# enzi_rev3.net
KiCad netlist of a schematic drawn in EAGLE
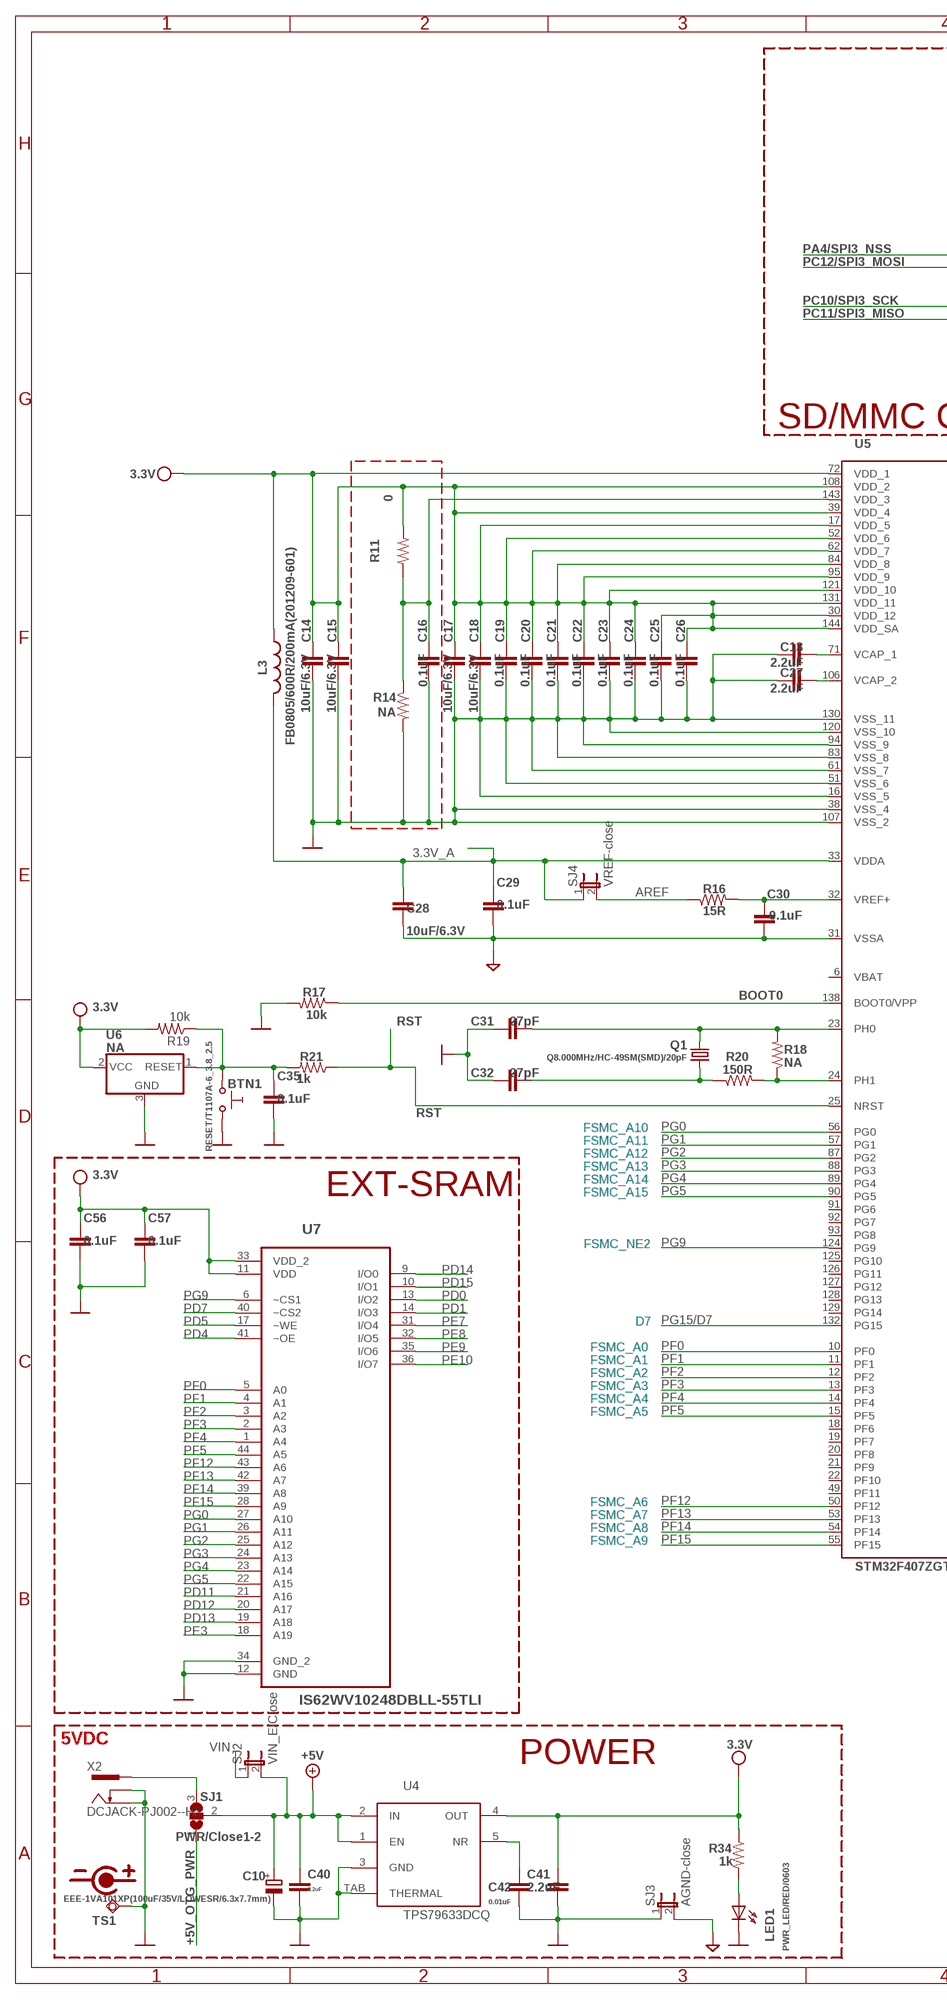
[diagram p0: schematic, sheet 1, part 1 of 2]
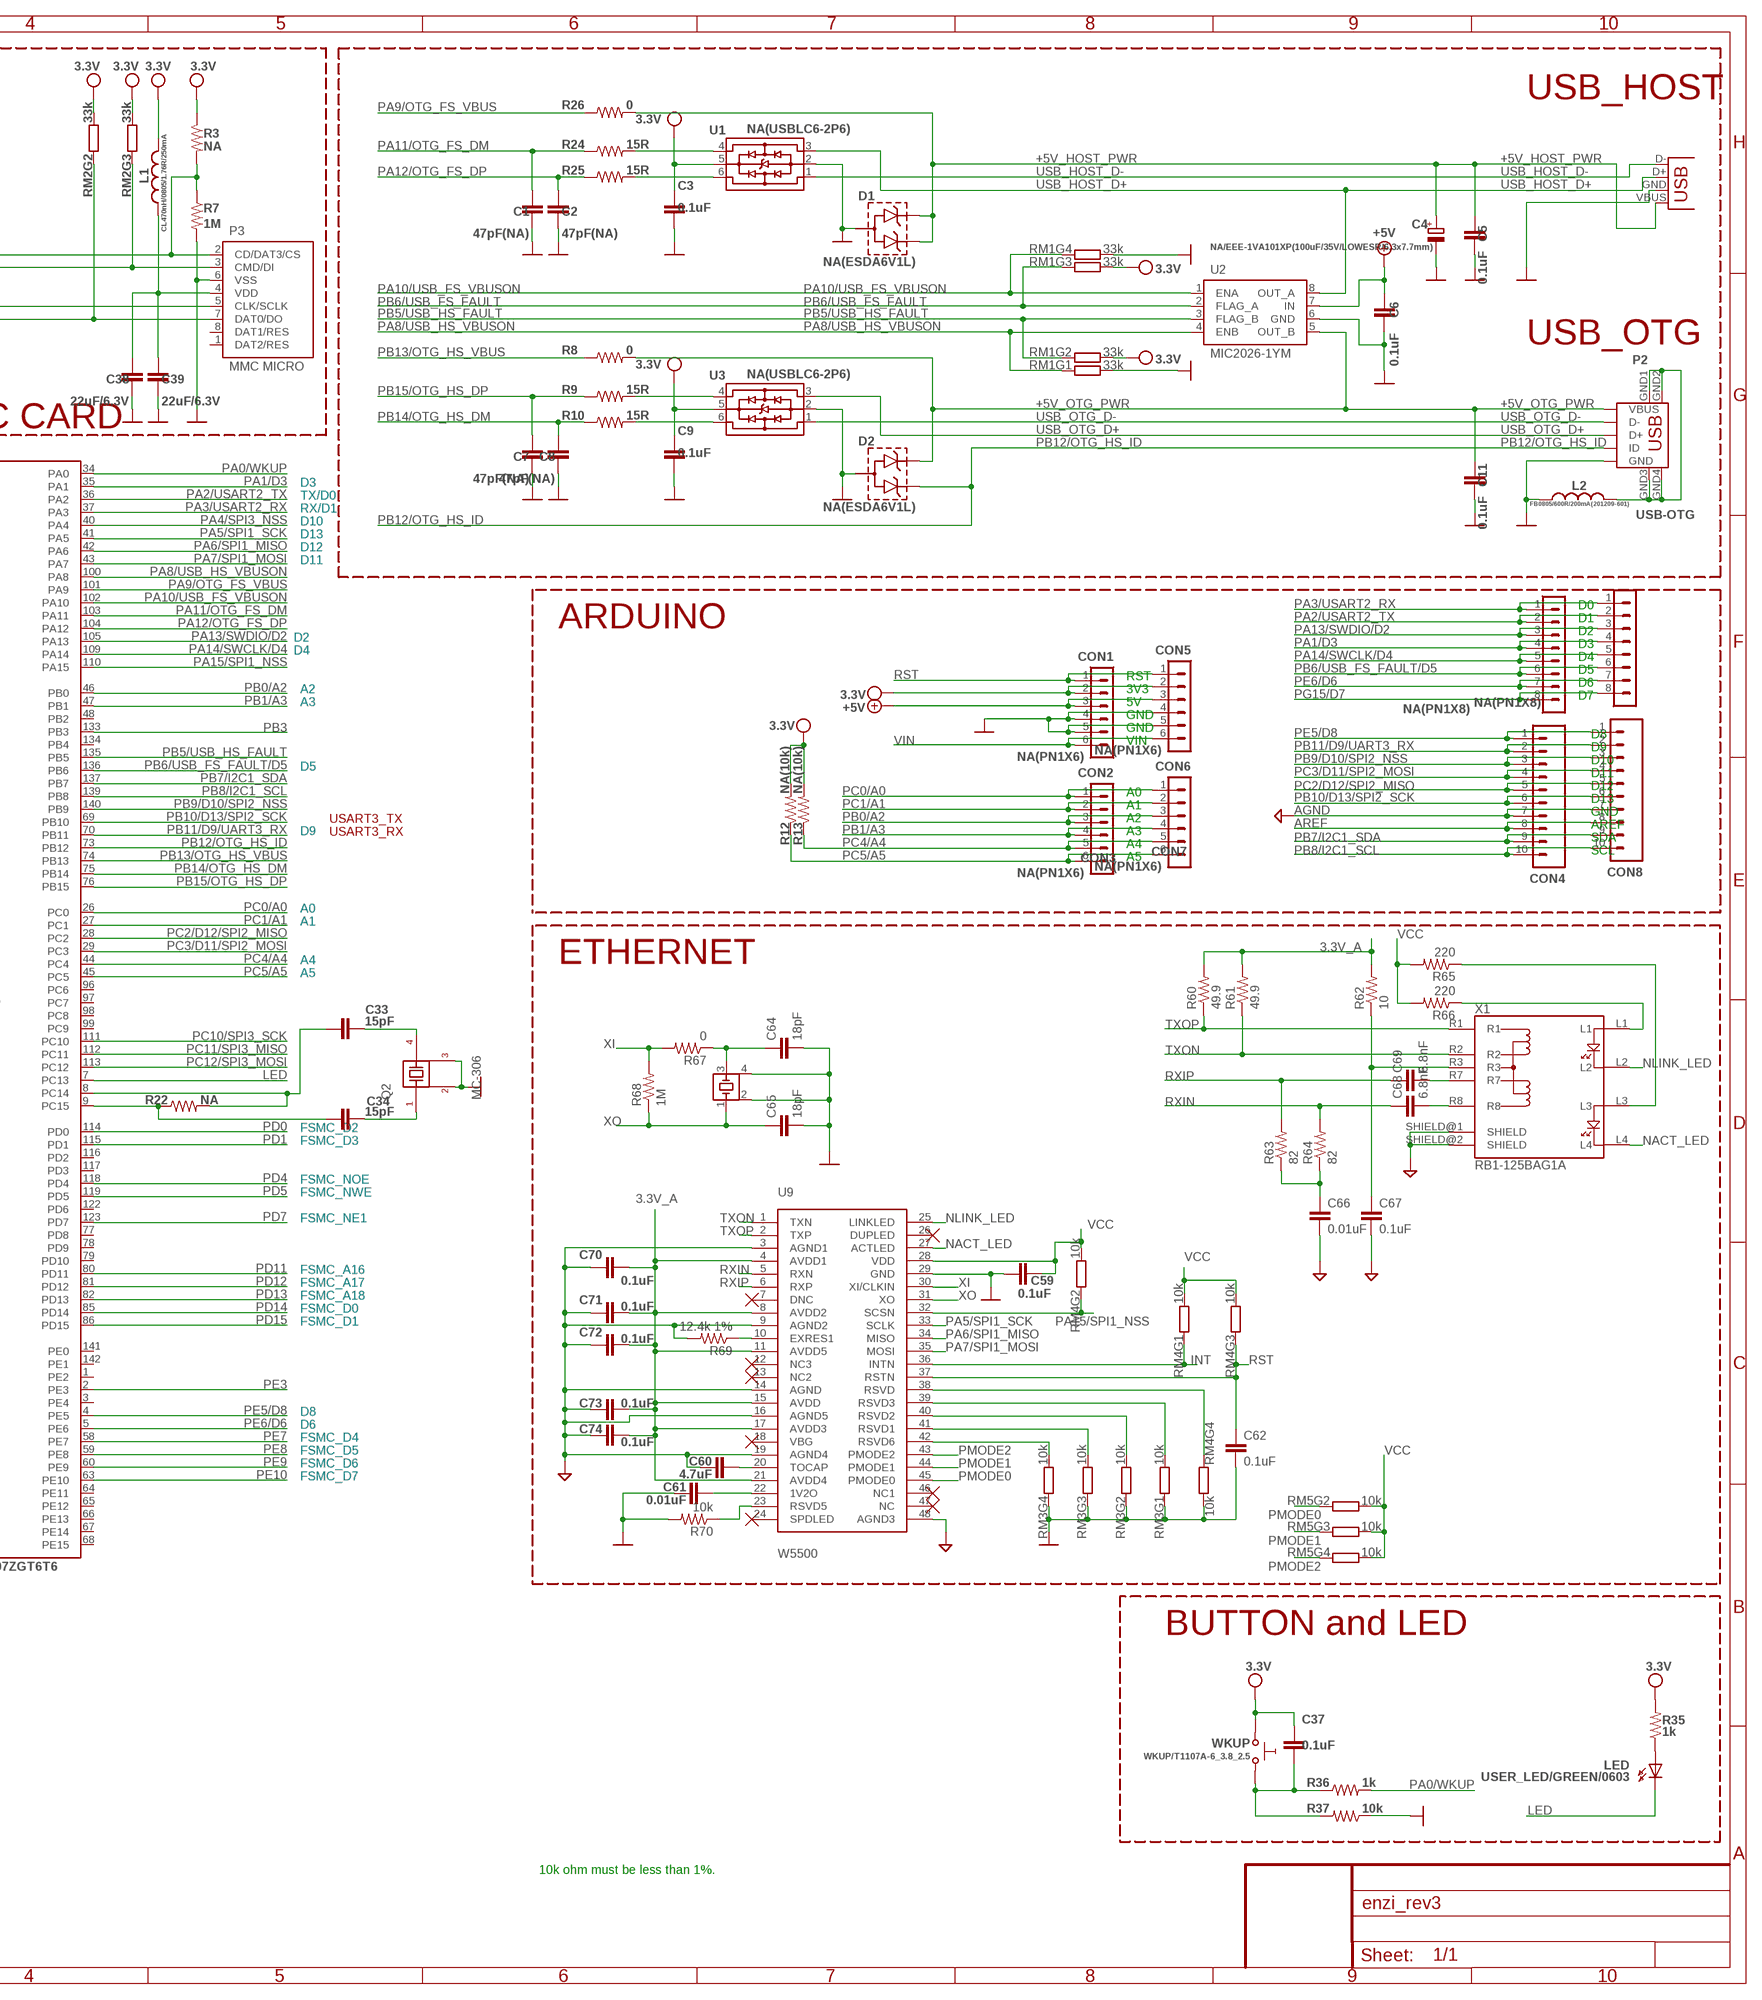
[diagram p1: schematic, sheet 1, part 2 of 2]

(export (version "E")
  (design (tool "Eeschema 10.0.6"))
  (components
    (comp (ref "BTN1")
      (value "RESET/T1107A-6_3.8_2.5")
      (footprint "eagle-import:SW-TAKT_6X3.5_SMD")
      (libsource (lib "eagle-import") (part "SW-TAKT6"))
    )
    (comp (ref "C1")
      (value "47pF(NA)")
      (footprint "eagle-import:0603-CAP")
      (libsource (lib "eagle-import") (part "CAP0603-CAP"))
    )
    (comp (ref "C2")
      (value "47pF(NA)")
      (footprint "eagle-import:0603-CAP")
      (libsource (lib "eagle-import") (part "CAP0603-CAP"))
    )
    (comp (ref "C3")
      (value "0.1uF")
      (footprint "eagle-import:0603-CAP")
      (libsource (lib "eagle-import") (part "CAP0603-CAP"))
    )
    (comp (ref "C4")
      (value "NA/EEE-1VA101XP(100uF/35V/LOWESR/6.3x7.7mm)")
      (footprint "eagle-import:PANASONIC_D")
      (libsource (lib "eagle-import") (part "CPOL-EUD"))
    )
    (comp (ref "C5")
      (value "0.1uF")
      (footprint "eagle-import:0603-CAP")
      (libsource (lib "eagle-import") (part "CAP0603-CAP"))
    )
    (comp (ref "C6")
      (value "0.1uF")
      (footprint "eagle-import:0603-CAP")
      (libsource (lib "eagle-import") (part "CAP0603-CAP"))
    )
    (comp (ref "C7")
      (value "47pF(NA)")
      (footprint "eagle-import:0603-CAP")
      (libsource (lib "eagle-import") (part "CAP0603-CAP"))
    )
    (comp (ref "C8")
      (value "47pF(NA)")
      (footprint "eagle-import:0603-CAP")
      (libsource (lib "eagle-import") (part "CAP0603-CAP"))
    )
    (comp (ref "C9")
      (value "0.1uF")
      (footprint "eagle-import:0603-CAP")
      (libsource (lib "eagle-import") (part "CAP0603-CAP"))
    )
    (comp (ref "C10")
      (value "EEE-1VA101XP(100uF/35V/LOWESR/6.3x7.7mm)")
      (footprint "eagle-import:PANASONIC_D")
      (libsource (lib "eagle-import") (part "CPOL-EUD"))
    )
    (comp (ref "C11")
      (value "0.1uF")
      (footprint "eagle-import:0603-CAP")
      (libsource (lib "eagle-import") (part "CAP0603-CAP"))
    )
    (comp (ref "C13")
      (value "2.2uF")
      (footprint "eagle-import:0603-CAP")
      (libsource (lib "eagle-import") (part "CAP0603-CAP"))
    )
    (comp (ref "C14")
      (value "10uF/6.3V")
      (footprint "eagle-import:0603-CAP")
      (libsource (lib "eagle-import") (part "CAP0603-CAP"))
    )
    (comp (ref "C15")
      (value "10uF/6.3V")
      (footprint "eagle-import:0603-CAP")
      (libsource (lib "eagle-import") (part "CAP0603-CAP"))
    )
    (comp (ref "C16")
      (value "0.1uF")
      (footprint "eagle-import:0603-CAP")
      (libsource (lib "eagle-import") (part "CAP0603-CAP"))
    )
    (comp (ref "C17")
      (value "10uF/6.3V")
      (footprint "eagle-import:0603-CAP")
      (libsource (lib "eagle-import") (part "CAP0603-CAP"))
    )
    (comp (ref "C18")
      (value "10uF/6.3V")
      (footprint "eagle-import:0603-CAP")
      (libsource (lib "eagle-import") (part "CAP0603-CAP"))
    )
    (comp (ref "C19")
      (value "0.1uF")
      (footprint "eagle-import:0603-CAP")
      (libsource (lib "eagle-import") (part "CAP0603-CAP"))
    )
    (comp (ref "C20")
      (value "0.1uF")
      (footprint "eagle-import:0603-CAP")
      (libsource (lib "eagle-import") (part "CAP0603-CAP"))
    )
    (comp (ref "C21")
      (value "0.1uF")
      (footprint "eagle-import:0603-CAP")
      (libsource (lib "eagle-import") (part "CAP0603-CAP"))
    )
    (comp (ref "C22")
      (value "0.1uF")
      (footprint "eagle-import:0603-CAP")
      (libsource (lib "eagle-import") (part "CAP0603-CAP"))
    )
    (comp (ref "C23")
      (value "0.1uF")
      (footprint "eagle-import:0603-CAP")
      (libsource (lib "eagle-import") (part "CAP0603-CAP"))
    )
    (comp (ref "C24")
      (value "0.1uF")
      (footprint "eagle-import:0603-CAP")
      (libsource (lib "eagle-import") (part "CAP0603-CAP"))
    )
    (comp (ref "C25")
      (value "0.1uF")
      (footprint "eagle-import:0603-CAP")
      (libsource (lib "eagle-import") (part "CAP0603-CAP"))
    )
    (comp (ref "C26")
      (value "0.1uF")
      (footprint "eagle-import:0603-CAP")
      (libsource (lib "eagle-import") (part "CAP0603-CAP"))
    )
    (comp (ref "C27")
      (value "2.2uF")
      (footprint "eagle-import:0603-CAP")
      (libsource (lib "eagle-import") (part "CAP0603-CAP"))
    )
    (comp (ref "C28")
      (value "10uF/6.3V")
      (footprint "eagle-import:0603-CAP")
      (libsource (lib "eagle-import") (part "CAP0603-CAP"))
    )
    (comp (ref "C29")
      (value "0.1uF")
      (footprint "eagle-import:0603-CAP")
      (libsource (lib "eagle-import") (part "CAP0603-CAP"))
    )
    (comp (ref "C30")
      (value "0.1uF")
      (footprint "eagle-import:0603-CAP")
      (libsource (lib "eagle-import") (part "CAP0603-CAP"))
    )
    (comp (ref "C31")
      (value "27pF")
      (footprint "eagle-import:0603-CAP")
      (libsource (lib "eagle-import") (part "CAP0603-CAP"))
    )
    (comp (ref "C32")
      (value "27pF")
      (footprint "eagle-import:0603-CAP")
      (libsource (lib "eagle-import") (part "CAP0603-CAP"))
    )
    (comp (ref "C33")
      (value "15pF")
      (footprint "eagle-import:0603-CAP")
      (libsource (lib "eagle-import") (part "CAP0603-CAP"))
    )
    (comp (ref "C34")
      (value "15pF")
      (footprint "eagle-import:0603-CAP")
      (libsource (lib "eagle-import") (part "CAP0603-CAP"))
    )
    (comp (ref "C35")
      (value "0.1uF")
      (footprint "eagle-import:0603-CAP")
      (libsource (lib "eagle-import") (part "CAP0603-CAP"))
    )
    (comp (ref "C37")
      (value "0.1uF")
      (footprint "eagle-import:0603-CAP")
      (libsource (lib "eagle-import") (part "CAP0603-CAP"))
    )
    (comp (ref "C38")
      (value "22uF/6.3V")
      (footprint "eagle-import:0603-CAP")
      (libsource (lib "eagle-import") (part "CAP0603-CAP"))
    )
    (comp (ref "C39")
      (value "22uF/6.3V")
      (footprint "eagle-import:0603-CAP")
      (libsource (lib "eagle-import") (part "CAP0603-CAP"))
    )
    (comp (ref "C40")
      (value "2.2uF")
      (footprint "eagle-import:0603-CAP")
      (libsource (lib "eagle-import") (part "CAP0603-CAP"))
    )
    (comp (ref "C41")
      (value "2.2uF")
      (footprint "eagle-import:0603-CAP")
      (libsource (lib "eagle-import") (part "CAP0603-CAP"))
    )
    (comp (ref "C42")
      (value "0.01uF")
      (footprint "eagle-import:0603-CAP")
      (libsource (lib "eagle-import") (part "CAP0603-CAP"))
    )
    (comp (ref "C56")
      (value "0.1uF")
      (footprint "eagle-import:0603-CAP")
      (libsource (lib "eagle-import") (part "CAP0603-CAP"))
    )
    (comp (ref "C57")
      (value "0.1uF")
      (footprint "eagle-import:0603-CAP")
      (libsource (lib "eagle-import") (part "CAP0603-CAP"))
    )
    (comp (ref "C59")
      (value "0.1uF")
      (footprint "eagle-import:0603-CAP")
      (libsource (lib "eagle-import") (part "CAP0603-CAP"))
    )
    (comp (ref "C60")
      (value "4.7uF")
      (footprint "eagle-import:0603-CAP")
      (libsource (lib "eagle-import") (part "CAP0603-CAP"))
    )
    (comp (ref "C61")
      (value "0.01uF")
      (footprint "eagle-import:0603-CAP")
      (libsource (lib "eagle-import") (part "CAP0603-CAP"))
    )
    (comp (ref "C62")
      (value "0.1uF")
      (footprint "eagle-import:0603-CAP")
      (libsource (lib "eagle-import") (part "CAP0603-CAP"))
    )
    (comp (ref "C64")
      (value "18pF")
      (footprint "eagle-import:0603-CAP")
      (libsource (lib "eagle-import") (part "CAP0603-CAP"))
    )
    (comp (ref "C65")
      (value "18pF")
      (footprint "eagle-import:0603-CAP")
      (libsource (lib "eagle-import") (part "CAP0603-CAP"))
    )
    (comp (ref "C66")
      (value "0.01uF")
      (footprint "eagle-import:0603-CAP")
      (libsource (lib "eagle-import") (part "CAP0603-CAP"))
    )
    (comp (ref "C67")
      (value "0.1uF")
      (footprint "eagle-import:0603-CAP")
      (libsource (lib "eagle-import") (part "CAP0603-CAP"))
    )
    (comp (ref "C68")
      (value "6.8nF")
      (footprint "eagle-import:0603-CAP")
      (libsource (lib "eagle-import") (part "CAP0603-CAP"))
    )
    (comp (ref "C69")
      (value "6.8nF")
      (footprint "eagle-import:0603-CAP")
      (libsource (lib "eagle-import") (part "CAP0603-CAP"))
    )
    (comp (ref "C70")
      (value "0.1uF")
      (footprint "eagle-import:0603-CAP")
      (libsource (lib "eagle-import") (part "CAP0603-CAP"))
    )
    (comp (ref "C71")
      (value "0.1uF")
      (footprint "eagle-import:0603-CAP")
      (libsource (lib "eagle-import") (part "CAP0603-CAP"))
    )
    (comp (ref "C72")
      (value "0.1uF")
      (footprint "eagle-import:0603-CAP")
      (libsource (lib "eagle-import") (part "CAP0603-CAP"))
    )
    (comp (ref "C73")
      (value "0.1uF")
      (footprint "eagle-import:0603-CAP")
      (libsource (lib "eagle-import") (part "CAP0603-CAP"))
    )
    (comp (ref "C74")
      (value "0.1uF")
      (footprint "eagle-import:0603-CAP")
      (libsource (lib "eagle-import") (part "CAP0603-CAP"))
    )
    (comp (ref "CON1")
      (value "NA(PN1X6)")
      (footprint "eagle-import:PN1X6")
      (libsource (lib "eagle-import") (part "CON6PN1X6"))
    )
    (comp (ref "CON2")
      (value "NA(PN1X6)")
      (footprint "eagle-import:PN1X6")
      (libsource (lib "eagle-import") (part "CON6PN1X6"))
    )
    (comp (ref "CON3")
      (value "NA(PN1X8)")
      (footprint "eagle-import:PN1X8")
      (libsource (lib "eagle-import") (part "CON8PN1X8"))
    )
    (comp (ref "CON4")
      (value "M10\"")
      (footprint "eagle-import:1X10")
      (libsource (lib "eagle-import") (part "M10{dblquote}"))
    )
    (comp (ref "CON5")
      (value "NA(PN1X6)")
      (footprint "eagle-import:PN1X6")
      (libsource (lib "eagle-import") (part "CON6PN1X6"))
    )
    (comp (ref "CON6")
      (value "NA(PN1X6)")
      (footprint "eagle-import:PN1X6")
      (libsource (lib "eagle-import") (part "CON6PN1X6"))
    )
    (comp (ref "CON7")
      (value "NA(PN1X8)")
      (footprint "eagle-import:PN1X8")
      (libsource (lib "eagle-import") (part "CON8PN1X8"))
    )
    (comp (ref "CON8")
      (value "M10\"")
      (footprint "eagle-import:1X10")
      (libsource (lib "eagle-import") (part "M10{dblquote}"))
    )
    (comp (ref "D1")
      (value "NA(ESDA6V1L)")
      (footprint "eagle-import:SOT-23")
      (libsource (lib "eagle-import") (part "MMBZ5V6ALT1"))
    )
    (comp (ref "D2")
      (value "NA(ESDA6V1L)")
      (footprint "eagle-import:SOT-23")
      (libsource (lib "eagle-import") (part "MMBZ5V6ALT1"))
    )
    (comp (ref "L1")
      (value "CL470nH/0805/1.76R/250mA")
      (footprint "eagle-import:L2012C")
      (libsource (lib "eagle-import") (part "L-USL2012C"))
    )
    (comp (ref "L2")
      (value "FB0805/600R/200mA(201209-601)")
      (footprint "eagle-import:L2012C")
      (libsource (lib "eagle-import") (part "L-USL2012C"))
    )
    (comp (ref "L3")
      (value "FB0805/600R/200mA(201209-601)")
      (footprint "eagle-import:L2012C")
      (libsource (lib "eagle-import") (part "L-USL2012C"))
    )
    (comp (ref "LED")
      (value "USER_LED/GREEN/0603")
      (footprint "eagle-import:LED-0603")
      (libsource (lib "eagle-import") (part "LED0603DWS"))
    )
    (comp (ref "LED1")
      (value "PWR_LED/RED/0603")
      (footprint "eagle-import:LED-0603")
      (libsource (lib "eagle-import") (part "LED0603DWS"))
    )
    (comp (ref "P2")
      (value "USB-OTG")
      (footprint "eagle-import:USB_MINI_9PIN")
      (libsource (lib "eagle-import") (part "MINI_USB9"))
    )
    (comp (ref "P3")
      (value "MMC MICRO")
      (footprint "eagle-import:TFR-MEM-CON")
      (libsource (lib "eagle-import") (part "MICRO_SD/MMC"))
    )
    (comp (ref "Q1")
      (value "Q8.000MHz/HC-49SM(SMD)/20pF")
      (footprint "eagle-import:HC49_SMD2_THIN")
      (libsource (lib "eagle-import") (part "HC49/S1"))
    )
    (comp (ref "Q2")
      (value "MC-306")
      (footprint "eagle-import:4-SOJ")
      (libsource (lib "eagle-import") (part "MC-306"))
    )
    (comp (ref "Q3")
      (value "25MHz/18pf")
      (footprint "eagle-import:ABRACON_CRYSTAL_5.0X3.2MM")
      (libsource (lib "eagle-import") (part "ABM3C-25.000MHZ-D4Y-T"))
    )
    (comp (ref "R3")
      (value "NA")
      (footprint "eagle-import:0603-RES")
      (libsource (lib "eagle-import") (part "RESISTOR0603-RES"))
    )
    (comp (ref "R7")
      (value "1M")
      (footprint "eagle-import:0603-RES")
      (libsource (lib "eagle-import") (part "RESISTOR0603-RES"))
    )
    (comp (ref "R8")
      (value "0")
      (footprint "eagle-import:0603-RES")
      (libsource (lib "eagle-import") (part "RESISTOR0603-RES"))
    )
    (comp (ref "R9")
      (value "15R")
      (footprint "eagle-import:0603-RES")
      (libsource (lib "eagle-import") (part "RESISTOR0603-RES"))
    )
    (comp (ref "R10")
      (value "15R")
      (footprint "eagle-import:0603-RES")
      (libsource (lib "eagle-import") (part "RESISTOR0603-RES"))
    )
    (comp (ref "R11")
      (value "0")
      (footprint "eagle-import:0603-RES")
      (libsource (lib "eagle-import") (part "RESISTOR0603-RES"))
    )
    (comp (ref "R12")
      (value "NA(10k)")
      (footprint "eagle-import:0603-RES")
      (libsource (lib "eagle-import") (part "RESISTOR0603-RES"))
    )
    (comp (ref "R13")
      (value "NA(10k)")
      (footprint "eagle-import:0603-RES")
      (libsource (lib "eagle-import") (part "RESISTOR0603-RES"))
    )
    (comp (ref "R14")
      (value "NA")
      (footprint "eagle-import:0603-RES")
      (libsource (lib "eagle-import") (part "RESISTOR0603-RES"))
    )
    (comp (ref "R16")
      (value "15R")
      (footprint "eagle-import:0603-RES")
      (libsource (lib "eagle-import") (part "RESISTOR0603-RES"))
    )
    (comp (ref "R17")
      (value "10k")
      (footprint "eagle-import:0603-RES")
      (libsource (lib "eagle-import") (part "RESISTOR0603-RES"))
    )
    (comp (ref "R18")
      (value "NA")
      (footprint "eagle-import:0603-RES")
      (libsource (lib "eagle-import") (part "RESISTOR0603-RES"))
    )
    (comp (ref "R19")
      (value "10k")
      (footprint "eagle-import:0603-RES")
      (libsource (lib "eagle-import") (part "RESISTOR0603-RES"))
    )
    (comp (ref "R20")
      (value "150R")
      (footprint "eagle-import:0603-RES")
      (libsource (lib "eagle-import") (part "RESISTOR0603-RES"))
    )
    (comp (ref "R21")
      (value "1k")
      (footprint "eagle-import:0603-RES")
      (libsource (lib "eagle-import") (part "RESISTOR0603-RES"))
    )
    (comp (ref "R22")
      (value "NA")
      (footprint "eagle-import:0603-RES")
      (libsource (lib "eagle-import") (part "RESISTOR0603-RES"))
    )
    (comp (ref "R24")
      (value "15R")
      (footprint "eagle-import:0603-RES")
      (libsource (lib "eagle-import") (part "RESISTOR0603-RES"))
    )
    (comp (ref "R25")
      (value "15R")
      (footprint "eagle-import:0603-RES")
      (libsource (lib "eagle-import") (part "RESISTOR0603-RES"))
    )
    (comp (ref "R26")
      (value "0")
      (footprint "eagle-import:0603-RES")
      (libsource (lib "eagle-import") (part "RESISTOR0603-RES"))
    )
    (comp (ref "R34")
      (value "1k")
      (footprint "eagle-import:0603-RES")
      (libsource (lib "eagle-import") (part "RESISTOR0603-RES"))
    )
    (comp (ref "R35")
      (value "1k")
      (footprint "eagle-import:0603-RES")
      (libsource (lib "eagle-import") (part "RESISTOR0603-RES"))
    )
    (comp (ref "R36")
      (value "1k")
      (footprint "eagle-import:0603-RES")
      (libsource (lib "eagle-import") (part "RESISTOR0603-RES"))
    )
    (comp (ref "R37")
      (value "10k")
      (footprint "eagle-import:0603-RES")
      (libsource (lib "eagle-import") (part "RESISTOR0603-RES"))
    )
    (comp (ref "R60")
      (value "49.9")
      (footprint "eagle-import:0603-RES")
      (libsource (lib "eagle-import") (part "RESISTOR0603-RES"))
    )
    (comp (ref "R61")
      (value "49.9")
      (footprint "eagle-import:0603-RES")
      (libsource (lib "eagle-import") (part "RESISTOR0603-RES"))
    )
    (comp (ref "R62")
      (value "10")
      (footprint "eagle-import:0603-RES")
      (libsource (lib "eagle-import") (part "RESISTOR0603-RES"))
    )
    (comp (ref "R63")
      (value "82")
      (footprint "eagle-import:0603-RES")
      (libsource (lib "eagle-import") (part "RESISTOR0603-RES"))
    )
    (comp (ref "R64")
      (value "82")
      (footprint "eagle-import:0603-RES")
      (libsource (lib "eagle-import") (part "RESISTOR0603-RES"))
    )
    (comp (ref "R65")
      (value "220")
      (footprint "eagle-import:0603-RES")
      (libsource (lib "eagle-import") (part "RESISTOR0603-RES"))
    )
    (comp (ref "R66")
      (value "220")
      (footprint "eagle-import:0603-RES")
      (libsource (lib "eagle-import") (part "RESISTOR0603-RES"))
    )
    (comp (ref "R67")
      (value "0")
      (footprint "eagle-import:0603-RES")
      (libsource (lib "eagle-import") (part "RESISTOR0603-RES"))
    )
    (comp (ref "R68")
      (value "1M")
      (footprint "eagle-import:0603-RES")
      (libsource (lib "eagle-import") (part "RESISTOR0603-RES"))
    )
    (comp (ref "R69")
      (value "12.4k 1%")
      (footprint "eagle-import:0603-RES")
      (libsource (lib "eagle-import") (part "RESISTOR0603-RES"))
    )
    (comp (ref "R70")
      (value "10k")
      (footprint "eagle-import:0603-RES")
      (libsource (lib "eagle-import") (part "RESISTOR0603-RES"))
    )
    (comp (ref "RM1")
      (value "33k")
      (footprint "eagle-import:R_MATRIX_4")
      (libsource (lib "eagle-import") (part "R_MATRIX_4E"))
    )
    (comp (ref "RM2")
      (value "33k")
      (footprint "eagle-import:R_MATRIX_4")
      (libsource (lib "eagle-import") (part "R_MATRIX_4E"))
    )
    (comp (ref "RM3")
      (value "10k")
      (footprint "eagle-import:R_MATRIX_4")
      (libsource (lib "eagle-import") (part "R_MATRIX_4E"))
    )
    (comp (ref "RM4")
      (value "10k")
      (footprint "eagle-import:R_MATRIX_4")
      (libsource (lib "eagle-import") (part "R_MATRIX_4E"))
    )
    (comp (ref "RM5")
      (value "10k")
      (footprint "eagle-import:R_MATRIX_4")
      (libsource (lib "eagle-import") (part "R_MATRIX_4E"))
    )
    (comp (ref "SJ1")
      (value "PWR/Close1-2")
      (footprint "eagle-import:SJ_2")
      (libsource (lib "eagle-import") (part "SJ2W"))
    )
    (comp (ref "SJ2")
      (value "VIN_E/Close")
      (footprint "eagle-import:SJ_2S")
      (libsource (lib "eagle-import") (part "JUMPER-2SMD-NC"))
    )
    (comp (ref "SJ3")
      (value "AGND-close")
      (footprint "eagle-import:SJ_2S")
      (libsource (lib "eagle-import") (part "JUMPER-2SMD-NC"))
    )
    (comp (ref "SJ4")
      (value "VREF-close")
      (footprint "eagle-import:SJ_2S")
      (libsource (lib "eagle-import") (part "JUMPER-2SMD-NC"))
    )
    (comp (ref "TS1")
      (value "TESTPAD3")
      (footprint "eagle-import:TEST_PAD40_70_SQUARE")
      (libsource (lib "eagle-import") (part "TESTPAD3"))
    )
    (comp (ref "U1")
      (value "NA(USBLC6-2P6)")
      (footprint "eagle-import:USBLC6-2P6")
      (libsource (lib "eagle-import") (part "USBLC6-2"))
    )
    (comp (ref "U2")
      (value "MIC2026-1YM")
      (footprint "eagle-import:SO-8")
      (libsource (lib "eagle-import") (part "MIC2026-1YM"))
    )
    (comp (ref "U3")
      (value "NA(USBLC6-2P6)")
      (footprint "eagle-import:USBLC6-2P6")
      (libsource (lib "eagle-import") (part "USBLC6-2"))
    )
    (comp (ref "U4")
      (value "TPS79633DCQ")
      (footprint "eagle-import:SOT223-5")
      (libsource (lib "eagle-import") (part "TPS79633DCQ"))
    )
    (comp (ref "U5")
      (value "STM32F407ZGT6T6")
      (footprint "eagle-import:LQFP144")
      (libsource (lib "eagle-import") (part "STM32F407ZGT6T6"))
    )
    (comp (ref "U6")
      (value "NA")
      (footprint "eagle-import:SOT23")
      (libsource (lib "eagle-import") (part "RESETMCP130T-300-I/TT"))
    )
    (comp (ref "U7")
      (value "IS62WV10248DBLL-55TLI")
      (footprint "eagle-import:SOP80P1176X120-44N")
      (libsource (lib "eagle-import") (part "IS62WV10248DBLL-55TLI"))
    )
    (comp (ref "U9")
      (value "W5500")
      (footprint "eagle-import:48LQFP")
      (libsource (lib "eagle-import") (part "W5500"))
    )
    (comp (ref "WKUP")
      (value "WKUP/T1107A-6_3.8_2.5")
      (footprint "eagle-import:SW-TAKT_6X3.5_SMD")
      (libsource (lib "eagle-import") (part "SW-TAKT6"))
    )
    (comp (ref "X1")
      (value "RB1-125BAG1A")
      (footprint "eagle-import:RB1-125BAG1A")
      (libsource (lib "eagle-import") (part "RB1-125BAG1A"))
    )
    (comp (ref "X2")
      (value "DCJACK-PJ002--H3")
      (footprint "eagle-import:PJ-002--H3")
      (libsource (lib "eagle-import") (part "DCJACK-PJ002--H3"))
    )
    (comp (ref "X3")
      (value "USB-A-HU")
      (footprint "eagle-import:USB-A-HU")
      (libsource (lib "eagle-import") (part "USB-A-HU"))
    )
  )
  (nets
    (net (code "1") (name "+5V") (class "Default")
      (node (ref "C10") (pin "+") (pinfunction "+_+") (pintype "passive"))
      (node (ref "C40") (pin "1") (pinfunction "1_1") (pintype "passive"))
      (node (ref "C6") (pin "1") (pinfunction "1_1") (pintype "passive"))
      (node (ref "CON1") (pin "3") (pinfunction "3_3") (pintype "passive"))
      (node (ref "CON5") (pin "3") (pinfunction "3_3") (pintype "passive"))
      (node (ref "SJ1") (pin "2") (pinfunction "2_2") (pintype "passive"))
      (node (ref "SJ2") (pin "2") (pinfunction "2_2") (pintype "passive"))
      (node (ref "U2") (pin "7") (pinfunction "IN_7") (pintype "input"))
      (node (ref "U4") (pin "1") (pinfunction "EN_1") (pintype "bidirectional"))
      (node (ref "U4") (pin "2") (pinfunction "IN_2") (pintype "bidirectional"))
    )
    (net (code "2") (name "/+5V_HOST_PWR") (class "Default")
      (node (ref "C4") (pin "+") (pinfunction "+_+") (pintype "passive"))
      (node (ref "C5") (pin "1") (pinfunction "1_1") (pintype "passive"))
      (node (ref "D1") (pin "1") (pinfunction "1_1") (pintype "passive"))
      (node (ref "D1") (pin "2") (pinfunction "2_2") (pintype "passive"))
      (node (ref "R26") (pin "2") (pinfunction "2_2") (pintype "passive"))
      (node (ref "X3") (pin "VBUS") (pinfunction "GND_VBUS") (pintype "bidirectional"))
    )
    (net (code "3") (name "/+5V_OTG_PWR") (class "Default")
      (node (ref "C11") (pin "1") (pinfunction "1_1") (pintype "passive"))
      (node (ref "D2") (pin "1") (pinfunction "1_1") (pintype "passive"))
      (node (ref "P2") (pin "VBUS") (pinfunction "VBUS_VBUS") (pintype "power_in"))
      (node (ref "R8") (pin "2") (pinfunction "2_2") (pintype "passive"))
      (node (ref "SJ1") (pin "1") (pinfunction "1_1") (pintype "passive"))
      (node (ref "U2") (pin "5") (pinfunction "OUT_B_5") (pintype "output"))
    )
    (net (code "4") (name "/3.3V_A") (class "Default")
      (node (ref "C28") (pin "1") (pinfunction "1_1") (pintype "passive"))
      (node (ref "C29") (pin "2") (pinfunction "2_2") (pintype "passive"))
      (node (ref "C70") (pin "2") (pinfunction "2_2") (pintype "passive"))
      (node (ref "C71") (pin "2") (pinfunction "2_2") (pintype "passive"))
      (node (ref "C72") (pin "2") (pinfunction "2_2") (pintype "passive"))
      (node (ref "C73") (pin "2") (pinfunction "2_2") (pintype "passive"))
      (node (ref "C74") (pin "2") (pinfunction "2_2") (pintype "passive"))
      (node (ref "L3") (pin "2") (pinfunction "2_2") (pintype "passive"))
      (node (ref "R60") (pin "2") (pinfunction "2_2") (pintype "passive"))
      (node (ref "R61") (pin "2") (pinfunction "2_2") (pintype "passive"))
      (node (ref "R62") (pin "2") (pinfunction "2_2") (pintype "passive"))
      (node (ref "SJ4") (pin "1") (pinfunction "1_1") (pintype "passive"))
      (node (ref "U5") (pin "33") (pinfunction "VDDA_33") (pintype "power_in"))
      (node (ref "U9") (pin "11") (pinfunction "AVDD5_11") (pintype "bidirectional"))
      (node (ref "U9") (pin "15") (pinfunction "AVDD_15") (pintype "bidirectional"))
      (node (ref "U9") (pin "17") (pinfunction "AVDD3_17") (pintype "bidirectional"))
      (node (ref "U9") (pin "21") (pinfunction "AVDD4_21") (pintype "bidirectional"))
      (node (ref "U9") (pin "4") (pinfunction "AVDD1_4") (pintype "bidirectional"))
      (node (ref "U9") (pin "8") (pinfunction "AVDD2_8") (pintype "bidirectional"))
    )
    (net (code "5") (name "/AREF") (class "Default")
      (node (ref "CON4") (pin "8") (pinfunction "8_8") (pintype "passive"))
      (node (ref "CON8") (pin "8") (pinfunction "8_8") (pintype "passive"))
      (node (ref "R16") (pin "1") (pinfunction "1_1") (pintype "passive"))
      (node (ref "SJ4") (pin "2") (pinfunction "2_2") (pintype "passive"))
    )
    (net (code "6") (name "/BOOT0") (class "Default")
      (node (ref "R17") (pin "1") (pinfunction "1_1") (pintype "passive"))
      (node (ref "U5") (pin "138") (pinfunction "BOOT0/VPP_138") (pintype "input"))
    )
    (net (code "7") (name "/INT") (class "Default")
      (node (ref "RM4") (pin "1.1") (pinfunction "1_1.1") (pintype "passive"))
      (node (ref "U9") (pin "36") (pinfunction "INTN_36") (pintype "bidirectional"))
    )
    (net (code "8") (name "/LED") (class "Default")
      (node (ref "LED") (pin "C") (pinfunction "C_C") (pintype "passive"))
      (node (ref "U5") (pin "7") (pinfunction "PC13_7") (pintype "bidirectional"))
    )
    (net (code "9") (name "/NACT_LED") (class "Default")
      (node (ref "U9") (pin "27") (pinfunction "ACTLED_27") (pintype "bidirectional"))
      (node (ref "X1") (pin "L4") (pinfunction "L4_L4") (pintype "bidirectional"))
    )
    (net (code "10") (name "/NLINK_LED") (class "Default")
      (node (ref "U9") (pin "25") (pinfunction "LINKLED_25") (pintype "bidirectional"))
      (node (ref "X1") (pin "L2") (pinfunction "L2_L2") (pintype "bidirectional"))
    )
    (net (code "11") (name "/PA0{slash}WKUP") (class "Default")
      (node (ref "R36") (pin "2") (pinfunction "2_2") (pintype "passive"))
      (node (ref "U5") (pin "34") (pinfunction "PA0_34") (pintype "bidirectional"))
    )
    (net (code "12") (name "/PA1{slash}D3") (class "Default")
      (node (ref "CON3") (pin "4") (pinfunction "4_4") (pintype "passive"))
      (node (ref "CON7") (pin "4") (pinfunction "4_4") (pintype "passive"))
      (node (ref "U5") (pin "35") (pinfunction "PA1_35") (pintype "bidirectional"))
    )
    (net (code "13") (name "/PA2{slash}USART2_TX") (class "Default")
      (node (ref "CON3") (pin "2") (pinfunction "2_2") (pintype "passive"))
      (node (ref "CON7") (pin "2") (pinfunction "2_2") (pintype "passive"))
      (node (ref "U5") (pin "36") (pinfunction "PA2_36") (pintype "bidirectional"))
    )
    (net (code "14") (name "/PA3{slash}USART2_RX") (class "Default")
      (node (ref "CON3") (pin "1") (pinfunction "1_1") (pintype "passive"))
      (node (ref "CON7") (pin "1") (pinfunction "1_1") (pintype "passive"))
      (node (ref "U5") (pin "37") (pinfunction "PA3_37") (pintype "bidirectional"))
    )
    (net (code "15") (name "/PA4{slash}SPI3_NSS") (class "Default")
      (node (ref "P3") (pin "2") (pinfunction "CD/DAT3/CS_2") (pintype "input"))
      (node (ref "R3") (pin "2") (pinfunction "2_2") (pintype "passive"))
      (node (ref "R7") (pin "1") (pinfunction "1_1") (pintype "passive"))
      (node (ref "U5") (pin "40") (pinfunction "PA4_40") (pintype "bidirectional"))
    )
    (net (code "16") (name "/PA5{slash}SPI1_SCK") (class "Default")
      (node (ref "U5") (pin "41") (pinfunction "PA5_41") (pintype "bidirectional"))
      (node (ref "U9") (pin "33") (pinfunction "SCLK_33") (pintype "bidirectional"))
    )
    (net (code "17") (name "/PA6{slash}SPI1_MISO") (class "Default")
      (node (ref "U5") (pin "42") (pinfunction "PA6_42") (pintype "bidirectional"))
      (node (ref "U9") (pin "34") (pinfunction "MISO_34") (pintype "bidirectional"))
    )
    (net (code "18") (name "/PA7{slash}SPI1_MOSI") (class "Default")
      (node (ref "U5") (pin "43") (pinfunction "PA7_43") (pintype "bidirectional"))
      (node (ref "U9") (pin "35") (pinfunction "MOSI_35") (pintype "bidirectional"))
    )
    (net (code "19") (name "/PA8{slash}USB_HS_VBUSON") (class "Default")
      (node (ref "RM1") (pin "1.1") (pinfunction "1_1.1") (pintype "passive"))
      (node (ref "U2") (pin "4") (pinfunction "ENB_4") (pintype "input"))
      (node (ref "U5") (pin "100") (pinfunction "PA8_100") (pintype "bidirectional"))
    )
    (net (code "20") (name "/PA9{slash}OTG_FS_VBUS") (class "Default")
      (node (ref "R26") (pin "1") (pinfunction "1_1") (pintype "passive"))
      (node (ref "U5") (pin "101") (pinfunction "PA9_101") (pintype "bidirectional"))
    )
    (net (code "21") (name "/PA10{slash}USB_FS_VBUSON") (class "Default")
      (node (ref "RM1") (pin "4.1") (pinfunction "1_4.1") (pintype "passive"))
      (node (ref "U2") (pin "1") (pinfunction "ENA_1") (pintype "input"))
      (node (ref "U5") (pin "102") (pinfunction "PA10_102") (pintype "bidirectional"))
    )
    (net (code "22") (name "/PA11{slash}OTG_FS_DM") (class "Default")
      (node (ref "C1") (pin "1") (pinfunction "1_1") (pintype "passive"))
      (node (ref "R24") (pin "1") (pinfunction "1_1") (pintype "passive"))
      (node (ref "U5") (pin "103") (pinfunction "PA11_103") (pintype "bidirectional"))
    )
    (net (code "23") (name "/PA12{slash}OTG_FS_DP") (class "Default")
      (node (ref "C2") (pin "1") (pinfunction "1_1") (pintype "passive"))
      (node (ref "R25") (pin "1") (pinfunction "1_1") (pintype "passive"))
      (node (ref "U5") (pin "104") (pinfunction "PA12_104") (pintype "bidirectional"))
    )
    (net (code "24") (name "/PA13{slash}SWDIO{slash}D2") (class "Default")
      (node (ref "CON3") (pin "3") (pinfunction "3_3") (pintype "passive"))
      (node (ref "CON7") (pin "3") (pinfunction "3_3") (pintype "passive"))
      (node (ref "U5") (pin "105") (pinfunction "PA13_105") (pintype "bidirectional"))
    )
    (net (code "25") (name "/PA14{slash}SWCLK{slash}D4") (class "Default")
      (node (ref "CON3") (pin "5") (pinfunction "5_5") (pintype "passive"))
      (node (ref "CON7") (pin "5") (pinfunction "5_5") (pintype "passive"))
      (node (ref "U5") (pin "109") (pinfunction "PA14_109") (pintype "bidirectional"))
    )
    (net (code "26") (name "/PA15{slash}SPI1_NSS") (class "Default")
      (node (ref "RM4") (pin "2.1") (pinfunction "1_2.1") (pintype "passive"))
      (node (ref "U5") (pin "110") (pinfunction "PA15_110") (pintype "bidirectional"))
      (node (ref "U9") (pin "32") (pinfunction "SCSN_32") (pintype "bidirectional"))
    )
    (net (code "27") (name "/PB0{slash}A2") (class "Default")
      (node (ref "CON2") (pin "3") (pinfunction "3_3") (pintype "passive"))
      (node (ref "CON6") (pin "3") (pinfunction "3_3") (pintype "passive"))
      (node (ref "U5") (pin "46") (pinfunction "PB0_46") (pintype "bidirectional"))
    )
    (net (code "28") (name "/PB1{slash}A3") (class "Default")
      (node (ref "CON2") (pin "4") (pinfunction "4_4") (pintype "passive"))
      (node (ref "CON6") (pin "4") (pinfunction "4_4") (pintype "passive"))
      (node (ref "U5") (pin "47") (pinfunction "PB1_47") (pintype "bidirectional"))
    )
    (net (code "29") (name "/PB3") (class "Default")
      (node (ref "U5") (pin "133") (pinfunction "PB3_133") (pintype "bidirectional"))
    )
    (net (code "30") (name "/PB5{slash}USB_HS_FAULT") (class "Default")
      (node (ref "RM1") (pin "2.1") (pinfunction "1_2.1") (pintype "passive"))
      (node (ref "U2") (pin "3") (pinfunction "FLAG_B_3") (pintype "open_collector"))
      (node (ref "U5") (pin "135") (pinfunction "PB5_135") (pintype "bidirectional"))
    )
    (net (code "31") (name "/PB6{slash}USB_FS_FAULT") (class "Default")
      (node (ref "RM1") (pin "3.1") (pinfunction "1_3.1") (pintype "passive"))
      (node (ref "U2") (pin "2") (pinfunction "FLAG_A_2") (pintype "open_collector"))
    )
    (net (code "32") (name "/PB6{slash}USB_FS_FAULT{slash}D5") (class "Default")
      (node (ref "CON3") (pin "6") (pinfunction "6_6") (pintype "passive"))
      (node (ref "CON7") (pin "6") (pinfunction "6_6") (pintype "passive"))
      (node (ref "U5") (pin "136") (pinfunction "PB6_136") (pintype "bidirectional"))
    )
    (net (code "33") (name "/PB7{slash}I2C1_SDA") (class "Default")
      (node (ref "CON4") (pin "9") (pinfunction "9_9") (pintype "passive"))
      (node (ref "CON8") (pin "9") (pinfunction "9_9") (pintype "passive"))
      (node (ref "U5") (pin "137") (pinfunction "PB7_137") (pintype "bidirectional"))
    )
    (net (code "34") (name "/PB8{slash}I2C1_SCL") (class "Default")
      (node (ref "CON4") (pin "10") (pinfunction "10_10") (pintype "passive"))
      (node (ref "CON8") (pin "10") (pinfunction "10_10") (pintype "passive"))
      (node (ref "U5") (pin "139") (pinfunction "PB8_139") (pintype "bidirectional"))
    )
    (net (code "35") (name "/PB9{slash}D10{slash}SPI2_NSS") (class "Default")
      (node (ref "CON4") (pin "3") (pinfunction "3_3") (pintype "passive"))
      (node (ref "CON8") (pin "3") (pinfunction "3_3") (pintype "passive"))
      (node (ref "U5") (pin "140") (pinfunction "PB9_140") (pintype "bidirectional"))
    )
    (net (code "36") (name "/PB10{slash}D13{slash}SPI2_SCK") (class "Default")
      (node (ref "CON4") (pin "6") (pinfunction "6_6") (pintype "passive"))
      (node (ref "CON8") (pin "6") (pinfunction "6_6") (pintype "passive"))
      (node (ref "U5") (pin "69") (pinfunction "PB10_69") (pintype "bidirectional"))
    )
    (net (code "37") (name "/PB11{slash}D9{slash}UART3_RX") (class "Default")
      (node (ref "CON4") (pin "2") (pinfunction "2_2") (pintype "passive"))
      (node (ref "CON8") (pin "2") (pinfunction "2_2") (pintype "passive"))
      (node (ref "U5") (pin "70") (pinfunction "PB11_70") (pintype "bidirectional"))
    )
    (net (code "38") (name "/PB12{slash}OTG_HS_ID") (class "Default")
      (node (ref "D2") (pin "2") (pinfunction "2_2") (pintype "passive"))
      (node (ref "P2") (pin "ID") (pinfunction "ID_ID") (pintype "input"))
      (node (ref "U5") (pin "73") (pinfunction "PB12_73") (pintype "bidirectional"))
    )
    (net (code "39") (name "/PB13{slash}OTG_HS_VBUS") (class "Default")
      (node (ref "R8") (pin "1") (pinfunction "1_1") (pintype "passive"))
      (node (ref "U5") (pin "74") (pinfunction "PB13_74") (pintype "bidirectional"))
    )
    (net (code "40") (name "/PB14{slash}OTG_HS_DM") (class "Default")
      (node (ref "C8") (pin "1") (pinfunction "1_1") (pintype "passive"))
      (node (ref "R10") (pin "1") (pinfunction "1_1") (pintype "passive"))
      (node (ref "U5") (pin "75") (pinfunction "PB14_75") (pintype "bidirectional"))
    )
    (net (code "41") (name "/PB15{slash}OTG_HS_DP") (class "Default")
      (node (ref "C7") (pin "1") (pinfunction "1_1") (pintype "passive"))
      (node (ref "R9") (pin "1") (pinfunction "1_1") (pintype "passive"))
      (node (ref "U5") (pin "76") (pinfunction "PB15_76") (pintype "bidirectional"))
    )
    (net (code "42") (name "/PC0{slash}A0") (class "Default")
      (node (ref "CON2") (pin "1") (pinfunction "1_1") (pintype "passive"))
      (node (ref "CON6") (pin "1") (pinfunction "1_1") (pintype "passive"))
      (node (ref "U5") (pin "26") (pinfunction "PC0_26") (pintype "bidirectional"))
    )
    (net (code "43") (name "/PC1{slash}A1") (class "Default")
      (node (ref "CON2") (pin "2") (pinfunction "2_2") (pintype "passive"))
      (node (ref "CON6") (pin "2") (pinfunction "2_2") (pintype "passive"))
      (node (ref "U5") (pin "27") (pinfunction "PC1_27") (pintype "bidirectional"))
    )
    (net (code "44") (name "/PC2{slash}D12{slash}SPI2_MISO") (class "Default")
      (node (ref "CON4") (pin "5") (pinfunction "5_5") (pintype "passive"))
      (node (ref "CON8") (pin "5") (pinfunction "5_5") (pintype "passive"))
      (node (ref "U5") (pin "28") (pinfunction "PC2_28") (pintype "bidirectional"))
    )
    (net (code "45") (name "/PC3{slash}D11{slash}SPI2_MOSI") (class "Default")
      (node (ref "CON4") (pin "4") (pinfunction "4_4") (pintype "passive"))
      (node (ref "CON8") (pin "4") (pinfunction "4_4") (pintype "passive"))
      (node (ref "U5") (pin "29") (pinfunction "PC3_29") (pintype "bidirectional"))
    )
    (net (code "46") (name "/PC4{slash}A4") (class "Default")
      (node (ref "CON2") (pin "5") (pinfunction "5_5") (pintype "passive"))
      (node (ref "CON6") (pin "5") (pinfunction "5_5") (pintype "passive"))
      (node (ref "R13") (pin "1") (pinfunction "1_1") (pintype "passive"))
      (node (ref "U5") (pin "44") (pinfunction "PC4_44") (pintype "bidirectional"))
    )
    (net (code "47") (name "/PC5{slash}A5") (class "Default")
      (node (ref "CON2") (pin "6") (pinfunction "6_6") (pintype "passive"))
      (node (ref "CON6") (pin "6") (pinfunction "6_6") (pintype "passive"))
      (node (ref "R12") (pin "1") (pinfunction "1_1") (pintype "passive"))
      (node (ref "U5") (pin "45") (pinfunction "PC5_45") (pintype "bidirectional"))
    )
    (net (code "48") (name "/PC10{slash}SPI3_SCK") (class "Default")
      (node (ref "P3") (pin "5") (pinfunction "CLK/SCLK_5") (pintype "input"))
      (node (ref "U5") (pin "111") (pinfunction "PC10_111") (pintype "bidirectional"))
    )
    (net (code "49") (name "/PC11{slash}SPI3_MISO") (class "Default")
      (node (ref "P3") (pin "7") (pinfunction "DAT0/DO_7") (pintype "output"))
      (node (ref "RM2") (pin "2.1") (pinfunction "1_2.1") (pintype "passive"))
      (node (ref "U5") (pin "112") (pinfunction "PC11_112") (pintype "bidirectional"))
    )
    (net (code "50") (name "/PC12{slash}SPI3_MOSI") (class "Default")
      (node (ref "P3") (pin "3") (pinfunction "CMD/DI_3") (pintype "input"))
      (node (ref "RM2") (pin "3.1") (pinfunction "1_3.1") (pintype "passive"))
      (node (ref "U5") (pin "113") (pinfunction "PC12_113") (pintype "bidirectional"))
    )
    (net (code "51") (name "/PD0") (class "Default")
      (node (ref "U5") (pin "114") (pinfunction "PD0_114") (pintype "bidirectional"))
      (node (ref "U7") (pin "13") (pinfunction "I/O2_13") (pintype "bidirectional"))
    )
    (net (code "52") (name "/PD1") (class "Default")
      (node (ref "U5") (pin "115") (pinfunction "PD1_115") (pintype "bidirectional"))
      (node (ref "U7") (pin "14") (pinfunction "I/O3_14") (pintype "bidirectional"))
    )
    (net (code "53") (name "/PD4") (class "Default")
      (node (ref "U5") (pin "118") (pinfunction "PD4_118") (pintype "bidirectional"))
      (node (ref "U7") (pin "41") (pinfunction "~{OE}_41") (pintype "input"))
    )
    (net (code "54") (name "/PD5") (class "Default")
      (node (ref "U5") (pin "119") (pinfunction "PD5_119") (pintype "bidirectional"))
      (node (ref "U7") (pin "17") (pinfunction "~{WE}_17") (pintype "input"))
    )
    (net (code "55") (name "/PD7") (class "Default")
      (node (ref "U5") (pin "123") (pinfunction "PD7_123") (pintype "bidirectional"))
      (node (ref "U7") (pin "40") (pinfunction "~{CS2}_40") (pintype "input"))
    )
    (net (code "56") (name "/PD11") (class "Default")
      (node (ref "U5") (pin "80") (pinfunction "PD11_80") (pintype "bidirectional"))
      (node (ref "U7") (pin "21") (pinfunction "A16_21") (pintype "input"))
    )
    (net (code "57") (name "/PD12") (class "Default")
      (node (ref "U5") (pin "81") (pinfunction "PD12_81") (pintype "bidirectional"))
      (node (ref "U7") (pin "20") (pinfunction "A17_20") (pintype "input"))
    )
    (net (code "58") (name "/PD13") (class "Default")
      (node (ref "U5") (pin "82") (pinfunction "PD13_82") (pintype "bidirectional"))
      (node (ref "U7") (pin "19") (pinfunction "A18_19") (pintype "input"))
    )
    (net (code "59") (name "/PD14") (class "Default")
      (node (ref "U5") (pin "85") (pinfunction "PD14_85") (pintype "bidirectional"))
      (node (ref "U7") (pin "9") (pinfunction "I/O0_9") (pintype "bidirectional"))
    )
    (net (code "60") (name "/PD15") (class "Default")
      (node (ref "U5") (pin "86") (pinfunction "PD15_86") (pintype "bidirectional"))
      (node (ref "U7") (pin "10") (pinfunction "I/O1_10") (pintype "bidirectional"))
    )
    (net (code "61") (name "/PE3") (class "Default")
      (node (ref "U5") (pin "2") (pinfunction "PE3_2") (pintype "bidirectional"))
      (node (ref "U7") (pin "18") (pinfunction "A19_18") (pintype "input"))
    )
    (net (code "62") (name "/PE5{slash}D8") (class "Default")
      (node (ref "CON4") (pin "1") (pinfunction "1_1") (pintype "passive"))
      (node (ref "CON8") (pin "1") (pinfunction "1_1") (pintype "passive"))
      (node (ref "U5") (pin "4") (pinfunction "PE5_4") (pintype "bidirectional"))
    )
    (net (code "63") (name "/PE6{slash}D6") (class "Default")
      (node (ref "CON3") (pin "7") (pinfunction "7_7") (pintype "passive"))
      (node (ref "CON7") (pin "7") (pinfunction "7_7") (pintype "passive"))
      (node (ref "U5") (pin "5") (pinfunction "PE6_5") (pintype "bidirectional"))
    )
    (net (code "64") (name "/PE7") (class "Default")
      (node (ref "U5") (pin "58") (pinfunction "PE7_58") (pintype "bidirectional"))
      (node (ref "U7") (pin "31") (pinfunction "I/O4_31") (pintype "bidirectional"))
    )
    (net (code "65") (name "/PE8") (class "Default")
      (node (ref "U5") (pin "59") (pinfunction "PE8_59") (pintype "bidirectional"))
      (node (ref "U7") (pin "32") (pinfunction "I/O5_32") (pintype "bidirectional"))
    )
    (net (code "66") (name "/PE9") (class "Default")
      (node (ref "U5") (pin "60") (pinfunction "PE9_60") (pintype "bidirectional"))
      (node (ref "U7") (pin "35") (pinfunction "I/O6_35") (pintype "bidirectional"))
    )
    (net (code "67") (name "/PE10") (class "Default")
      (node (ref "U5") (pin "63") (pinfunction "PE10_63") (pintype "bidirectional"))
      (node (ref "U7") (pin "36") (pinfunction "I/O7_36") (pintype "bidirectional"))
    )
    (net (code "68") (name "/PF0") (class "Default")
      (node (ref "U5") (pin "10") (pinfunction "PF0_10") (pintype "bidirectional"))
      (node (ref "U7") (pin "5") (pinfunction "A0_5") (pintype "input"))
    )
    (net (code "69") (name "/PF1") (class "Default")
      (node (ref "U5") (pin "11") (pinfunction "PF1_11") (pintype "bidirectional"))
      (node (ref "U7") (pin "4") (pinfunction "A1_4") (pintype "input"))
    )
    (net (code "70") (name "/PF2") (class "Default")
      (node (ref "U5") (pin "12") (pinfunction "PF2_12") (pintype "bidirectional"))
      (node (ref "U7") (pin "3") (pinfunction "A2_3") (pintype "input"))
    )
    (net (code "71") (name "/PF3") (class "Default")
      (node (ref "U5") (pin "13") (pinfunction "PF3_13") (pintype "bidirectional"))
      (node (ref "U7") (pin "2") (pinfunction "A3_2") (pintype "input"))
    )
    (net (code "72") (name "/PF4") (class "Default")
      (node (ref "U5") (pin "14") (pinfunction "PF4_14") (pintype "bidirectional"))
      (node (ref "U7") (pin "1") (pinfunction "A4_1") (pintype "input"))
    )
    (net (code "73") (name "/PF5") (class "Default")
      (node (ref "U5") (pin "15") (pinfunction "PF5_15") (pintype "bidirectional"))
      (node (ref "U7") (pin "44") (pinfunction "A5_44") (pintype "input"))
    )
    (net (code "74") (name "/PF12") (class "Default")
      (node (ref "U5") (pin "50") (pinfunction "PF12_50") (pintype "bidirectional"))
      (node (ref "U7") (pin "43") (pinfunction "A6_43") (pintype "input"))
    )
    (net (code "75") (name "/PF13") (class "Default")
      (node (ref "U5") (pin "53") (pinfunction "PF13_53") (pintype "bidirectional"))
      (node (ref "U7") (pin "42") (pinfunction "A7_42") (pintype "input"))
    )
    (net (code "76") (name "/PF14") (class "Default")
      (node (ref "U5") (pin "54") (pinfunction "PF14_54") (pintype "bidirectional"))
      (node (ref "U7") (pin "39") (pinfunction "A8_39") (pintype "input"))
    )
    (net (code "77") (name "/PF15") (class "Default")
      (node (ref "U5") (pin "55") (pinfunction "PF15_55") (pintype "bidirectional"))
      (node (ref "U7") (pin "28") (pinfunction "A9_28") (pintype "input"))
    )
    (net (code "78") (name "/PG0") (class "Default")
      (node (ref "U5") (pin "56") (pinfunction "PG0_56") (pintype "bidirectional"))
      (node (ref "U7") (pin "27") (pinfunction "A10_27") (pintype "input"))
    )
    (net (code "79") (name "/PG1") (class "Default")
      (node (ref "U5") (pin "57") (pinfunction "PG1_57") (pintype "bidirectional"))
      (node (ref "U7") (pin "26") (pinfunction "A11_26") (pintype "input"))
    )
    (net (code "80") (name "/PG2") (class "Default")
      (node (ref "U5") (pin "87") (pinfunction "PG2_87") (pintype "bidirectional"))
      (node (ref "U7") (pin "25") (pinfunction "A12_25") (pintype "input"))
    )
    (net (code "81") (name "/PG3") (class "Default")
      (node (ref "U5") (pin "88") (pinfunction "PG3_88") (pintype "bidirectional"))
      (node (ref "U7") (pin "24") (pinfunction "A13_24") (pintype "input"))
    )
    (net (code "82") (name "/PG4") (class "Default")
      (node (ref "U5") (pin "89") (pinfunction "PG4_89") (pintype "bidirectional"))
      (node (ref "U7") (pin "23") (pinfunction "A14_23") (pintype "input"))
    )
    (net (code "83") (name "/PG5") (class "Default")
      (node (ref "U5") (pin "90") (pinfunction "PG5_90") (pintype "bidirectional"))
      (node (ref "U7") (pin "22") (pinfunction "A15_22") (pintype "input"))
    )
    (net (code "84") (name "/PG9") (class "Default")
      (node (ref "U5") (pin "124") (pinfunction "PG9_124") (pintype "bidirectional"))
      (node (ref "U7") (pin "6") (pinfunction "~{CS1}_6") (pintype "input"))
    )
    (net (code "85") (name "/PG15{slash}D7") (class "Default")
      (node (ref "CON3") (pin "8") (pinfunction "8_8") (pintype "passive"))
      (node (ref "CON7") (pin "8") (pinfunction "8_8") (pintype "passive"))
      (node (ref "U5") (pin "132") (pinfunction "PG15_132") (pintype "bidirectional"))
    )
    (net (code "86") (name "/PMODE0") (class "Default")
      (node (ref "RM5") (pin "2.1") (pinfunction "1_2.1") (pintype "passive"))
      (node (ref "U9") (pin "45") (pinfunction "PMODE0_45") (pintype "bidirectional"))
    )
    (net (code "87") (name "/PMODE1") (class "Default")
      (node (ref "RM5") (pin "3.1") (pinfunction "1_3.1") (pintype "passive"))
      (node (ref "U9") (pin "44") (pinfunction "PMODE1_44") (pintype "bidirectional"))
    )
    (net (code "88") (name "/PMODE2") (class "Default")
      (node (ref "RM5") (pin "4.1") (pinfunction "1_4.1") (pintype "passive"))
      (node (ref "U9") (pin "43") (pinfunction "PMODE2_43") (pintype "bidirectional"))
    )
    (net (code "89") (name "/RST") (class "Default")
      (node (ref "C62") (pin "1") (pinfunction "1_1") (pintype "passive"))
      (node (ref "CON1") (pin "1") (pinfunction "1_1") (pintype "passive"))
      (node (ref "CON5") (pin "1") (pinfunction "1_1") (pintype "passive"))
      (node (ref "R21") (pin "1") (pinfunction "1_1") (pintype "passive"))
      (node (ref "RM4") (pin "3.1") (pinfunction "1_3.1") (pintype "passive"))
      (node (ref "U5") (pin "25") (pinfunction "NRST_25") (pintype "power_in"))
      (node (ref "U9") (pin "37") (pinfunction "RSTN_37") (pintype "bidirectional"))
    )
    (net (code "90") (name "/RXIN") (class "Default")
      (node (ref "C68") (pin "1") (pinfunction "1_1") (pintype "passive"))
      (node (ref "R64") (pin "2") (pinfunction "2_2") (pintype "passive"))
      (node (ref "U9") (pin "5") (pinfunction "RXN_5") (pintype "bidirectional"))
    )
    (net (code "91") (name "/RXIP") (class "Default")
      (node (ref "C69") (pin "1") (pinfunction "1_1") (pintype "passive"))
      (node (ref "R63") (pin "2") (pinfunction "2_2") (pintype "passive"))
      (node (ref "U9") (pin "6") (pinfunction "RXP_6") (pintype "bidirectional"))
    )
    (net (code "92") (name "/TXON") (class "Default")
      (node (ref "R61") (pin "1") (pinfunction "1_1") (pintype "passive"))
      (node (ref "U9") (pin "1") (pinfunction "TXN_1") (pintype "bidirectional"))
      (node (ref "X1") (pin "R2") (pinfunction "R2_R2") (pintype "bidirectional"))
    )
    (net (code "93") (name "/TXOP") (class "Default")
      (node (ref "R60") (pin "1") (pinfunction "1_1") (pintype "passive"))
      (node (ref "U9") (pin "2") (pinfunction "TXP_2") (pintype "bidirectional"))
      (node (ref "X1") (pin "R1") (pinfunction "R1_R1") (pintype "bidirectional"))
    )
    (net (code "94") (name "/USB_HOST_D+") (class "Default")
      (node (ref "U1") (pin "3") (pinfunction "3_3") (pintype "bidirectional"))
      (node (ref "U2") (pin "8") (pinfunction "OUT_A_8") (pintype "output"))
      (node (ref "X3") (pin "D+") (pinfunction "D-_D+") (pintype "bidirectional"))
    )
    (net (code "95") (name "/USB_HOST_D-") (class "Default")
      (node (ref "U1") (pin "1") (pinfunction "1_1") (pintype "bidirectional"))
      (node (ref "X3") (pin "D-") (pinfunction "D+_D-") (pintype "bidirectional"))
    )
    (net (code "96") (name "/USB_OTG_D+") (class "Default")
      (node (ref "P2") (pin "D+") (pinfunction "D+_D+") (pintype "input"))
      (node (ref "U3") (pin "3") (pinfunction "3_3") (pintype "bidirectional"))
    )
    (net (code "97") (name "/USB_OTG_D-") (class "Default")
      (node (ref "P2") (pin "D-") (pinfunction "D-_D-") (pintype "input"))
      (node (ref "U3") (pin "1") (pinfunction "1_1") (pintype "bidirectional"))
    )
    (net (code "98") (name "/VBAT") (class "Default")
      (node (ref "U5") (pin "6") (pinfunction "VBAT_6") (pintype "power_in"))
    )
    (net (code "99") (name "/VIN") (class "Default")
      (node (ref "CON1") (pin "6") (pinfunction "6_6") (pintype "passive"))
      (node (ref "CON5") (pin "6") (pinfunction "6_6") (pintype "passive"))
      (node (ref "SJ2") (pin "1") (pinfunction "1_1") (pintype "passive"))
    )
    (net (code "100") (name "/XI") (class "Default")
      (node (ref "R67") (pin "2") (pinfunction "2_2") (pintype "passive"))
      (node (ref "R68") (pin "2") (pinfunction "2_2") (pintype "passive"))
      (node (ref "U9") (pin "30") (pinfunction "XI/CLKIN_30") (pintype "bidirectional"))
    )
    (net (code "101") (name "/XO") (class "Default")
      (node (ref "C65") (pin "1") (pinfunction "1_1") (pintype "passive"))
      (node (ref "Q3") (pin "1") (pinfunction "1_1") (pintype "bidirectional"))
      (node (ref "R68") (pin "1") (pinfunction "1_1") (pintype "passive"))
      (node (ref "U9") (pin "31") (pinfunction "XO_31") (pintype "bidirectional"))
    )
    (net (code "102") (name "3.3V") (class "Default")
      (node (ref "C14") (pin "2") (pinfunction "2_2") (pintype "passive"))
      (node (ref "C15") (pin "2") (pinfunction "2_2") (pintype "passive"))
      (node (ref "C17") (pin "2") (pinfunction "2_2") (pintype "passive"))
      (node (ref "C18") (pin "2") (pinfunction "2_2") (pintype "passive"))
      (node (ref "C19") (pin "2") (pinfunction "2_2") (pintype "passive"))
      (node (ref "C20") (pin "2") (pinfunction "2_2") (pintype "passive"))
      (node (ref "C21") (pin "2") (pinfunction "2_2") (pintype "passive"))
      (node (ref "C22") (pin "2") (pinfunction "2_2") (pintype "passive"))
      (node (ref "C23") (pin "2") (pinfunction "2_2") (pintype "passive"))
      (node (ref "C24") (pin "2") (pinfunction "2_2") (pintype "passive"))
      (node (ref "C25") (pin "2") (pinfunction "2_2") (pintype "passive"))
      (node (ref "C26") (pin "2") (pinfunction "2_2") (pintype "passive"))
      (node (ref "C3") (pin "2") (pinfunction "2_2") (pintype "passive"))
      (node (ref "C37") (pin "2") (pinfunction "2_2") (pintype "passive"))
      (node (ref "C41") (pin "1") (pinfunction "1_1") (pintype "passive"))
      (node (ref "C56") (pin "2") (pinfunction "2_2") (pintype "passive"))
      (node (ref "C57") (pin "2") (pinfunction "2_2") (pintype "passive"))
      (node (ref "C59") (pin "1") (pinfunction "1_1") (pintype "passive"))
      (node (ref "C9") (pin "2") (pinfunction "2_2") (pintype "passive"))
      (node (ref "CON1") (pin "2") (pinfunction "2_2") (pintype "passive"))
      (node (ref "CON5") (pin "2") (pinfunction "2_2") (pintype "passive"))
      (node (ref "L1") (pin "1") (pinfunction "1_1") (pintype "passive"))
      (node (ref "L3") (pin "1") (pinfunction "1_1") (pintype "passive"))
      (node (ref "R11") (pin "2") (pinfunction "2_2") (pintype "passive"))
      (node (ref "R12") (pin "2") (pinfunction "2_2") (pintype "passive"))
      (node (ref "R13") (pin "2") (pinfunction "2_2") (pintype "passive"))
      (node (ref "R19") (pin "2") (pinfunction "2_2") (pintype "passive"))
      (node (ref "R3") (pin "1") (pinfunction "1_1") (pintype "passive"))
      (node (ref "R34") (pin "1") (pinfunction "1_1") (pintype "passive"))
      (node (ref "R35") (pin "2") (pinfunction "2_2") (pintype "passive"))
      (node (ref "R65") (pin "2") (pinfunction "2_2") (pintype "passive"))
      (node (ref "R66") (pin "2") (pinfunction "2_2") (pintype "passive"))
      (node (ref "RM1") (pin "2.2") (pinfunction "2_2.2") (pintype "passive"))
      (node (ref "RM1") (pin "3.2") (pinfunction "2_3.2") (pintype "passive"))
      (node (ref "RM2") (pin "2.2") (pinfunction "2_2.2") (pintype "passive"))
      (node (ref "RM2") (pin "3.2") (pinfunction "2_3.2") (pintype "passive"))
      (node (ref "RM4") (pin "1.2") (pinfunction "2_1.2") (pintype "passive"))
      (node (ref "RM4") (pin "2.2") (pinfunction "2_2.2") (pintype "passive"))
      (node (ref "RM4") (pin "3.2") (pinfunction "2_3.2") (pintype "passive"))
      (node (ref "RM5") (pin "2.2") (pinfunction "2_2.2") (pintype "passive"))
      (node (ref "RM5") (pin "3.2") (pinfunction "2_3.2") (pintype "passive"))
      (node (ref "RM5") (pin "4.2") (pinfunction "2_4.2") (pintype "passive"))
      (node (ref "U1") (pin "5") (pinfunction "5_5") (pintype "power_in"))
      (node (ref "U3") (pin "5") (pinfunction "5_5") (pintype "power_in"))
      (node (ref "U4") (pin "4") (pinfunction "OUT_4") (pintype "bidirectional"))
      (node (ref "U5") (pin "108") (pinfunction "VDD_2_108") (pintype "power_in"))
      (node (ref "U5") (pin "121") (pinfunction "VDD_10_121") (pintype "power_in"))
      (node (ref "U5") (pin "131") (pinfunction "VDD_11_131") (pintype "power_in"))
      (node (ref "U5") (pin "144") (pinfunction "VDD_SA_144") (pintype "power_in"))
      (node (ref "U5") (pin "17") (pinfunction "VDD_5_17") (pintype "power_in"))
      (node (ref "U5") (pin "30") (pinfunction "VDD_12_30") (pintype "power_in"))
      (node (ref "U5") (pin "39") (pinfunction "VDD_4_39") (pintype "power_in"))
      (node (ref "U5") (pin "52") (pinfunction "VDD_6_52") (pintype "power_in"))
      (node (ref "U5") (pin "62") (pinfunction "VDD_7_62") (pintype "power_in"))
      (node (ref "U5") (pin "72") (pinfunction "VDD_1_72") (pintype "power_in"))
      (node (ref "U5") (pin "84") (pinfunction "VDD_8_84") (pintype "power_in"))
      (node (ref "U5") (pin "95") (pinfunction "VDD_9_95") (pintype "power_in"))
      (node (ref "U6") (pin "2") (pinfunction "VCC_2") (pintype "power_in"))
      (node (ref "U7") (pin "11") (pinfunction "VDD_11") (pintype "power_in"))
      (node (ref "U7") (pin "33") (pinfunction "VDD_2_33") (pintype "power_in"))
      (node (ref "U9") (pin "28") (pinfunction "VDD_28") (pintype "bidirectional"))
      (node (ref "WKUP") (pin "P$1") (pinfunction "0_P$1") (pintype "passive"))
    )
    (net (code "103") (name "AGND") (class "Default")
      (node (ref "C28") (pin "2") (pinfunction "2_2") (pintype "passive"))
      (node (ref "C29") (pin "1") (pinfunction "1_1") (pintype "passive"))
      (node (ref "C30") (pin "1") (pinfunction "1_1") (pintype "passive"))
      (node (ref "C60") (pin "1") (pinfunction "1_1") (pintype "passive"))
      (node (ref "C66") (pin "2") (pinfunction "2_2") (pintype "passive"))
      (node (ref "C67") (pin "2") (pinfunction "2_2") (pintype "passive"))
      (node (ref "C70") (pin "1") (pinfunction "1_1") (pintype "passive"))
      (node (ref "C71") (pin "1") (pinfunction "1_1") (pintype "passive"))
      (node (ref "C72") (pin "1") (pinfunction "1_1") (pintype "passive"))
      (node (ref "C73") (pin "1") (pinfunction "1_1") (pintype "passive"))
      (node (ref "C74") (pin "1") (pinfunction "1_1") (pintype "passive"))
      (node (ref "CON4") (pin "7") (pinfunction "7_7") (pintype "passive"))
      (node (ref "CON8") (pin "7") (pinfunction "7_7") (pintype "passive"))
      (node (ref "R69") (pin "2") (pinfunction "2_2") (pintype "passive"))
      (node (ref "SJ3") (pin "2") (pinfunction "2_2") (pintype "passive"))
      (node (ref "U5") (pin "31") (pinfunction "VSSA_31") (pintype "power_in"))
      (node (ref "U9") (pin "14") (pinfunction "AGND_14") (pintype "bidirectional"))
      (node (ref "U9") (pin "16") (pinfunction "AGND5_16") (pintype "bidirectional"))
      (node (ref "U9") (pin "19") (pinfunction "AGND4_19") (pintype "bidirectional"))
      (node (ref "U9") (pin "3") (pinfunction "AGND1_3") (pintype "bidirectional"))
      (node (ref "U9") (pin "48") (pinfunction "AGND3_48") (pintype "bidirectional"))
      (node (ref "U9") (pin "9") (pinfunction "AGND2_9") (pintype "bidirectional"))
      (node (ref "X1") (pin "SHIELD@1") (pinfunction "SHIELD_SHIELD@1") (pintype "bidirectional"))
      (node (ref "X1") (pin "SHIELD@2") (pinfunction "SHIELD_SHIELD@2") (pintype "bidirectional"))
    )
    (net (code "104") (name "GND") (class "Default")
      (node (ref "BTN1") (pin "P$2") (pinfunction "1_P$2") (pintype "passive"))
      (node (ref "C1") (pin "2") (pinfunction "2_2") (pintype "passive"))
      (node (ref "C10") (pin "-") (pinfunction "-_-") (pintype "passive"))
      (node (ref "C11") (pin "2") (pinfunction "2_2") (pintype "passive"))
      (node (ref "C13") (pin "1") (pinfunction "1_1") (pintype "passive"))
      (node (ref "C14") (pin "1") (pinfunction "1_1") (pintype "passive"))
      (node (ref "C15") (pin "1") (pinfunction "1_1") (pintype "passive"))
      (node (ref "C16") (pin "1") (pinfunction "1_1") (pintype "passive"))
      (node (ref "C17") (pin "1") (pinfunction "1_1") (pintype "passive"))
      (node (ref "C18") (pin "1") (pinfunction "1_1") (pintype "passive"))
      (node (ref "C19") (pin "1") (pinfunction "1_1") (pintype "passive"))
      (node (ref "C2") (pin "2") (pinfunction "2_2") (pintype "passive"))
      (node (ref "C20") (pin "1") (pinfunction "1_1") (pintype "passive"))
      (node (ref "C21") (pin "1") (pinfunction "1_1") (pintype "passive"))
      (node (ref "C22") (pin "1") (pinfunction "1_1") (pintype "passive"))
      (node (ref "C23") (pin "1") (pinfunction "1_1") (pintype "passive"))
      (node (ref "C24") (pin "1") (pinfunction "1_1") (pintype "passive"))
      (node (ref "C25") (pin "1") (pinfunction "1_1") (pintype "passive"))
      (node (ref "C26") (pin "1") (pinfunction "1_1") (pintype "passive"))
      (node (ref "C27") (pin "1") (pinfunction "1_1") (pintype "passive"))
      (node (ref "C3") (pin "1") (pinfunction "1_1") (pintype "passive"))
      (node (ref "C31") (pin "2") (pinfunction "2_2") (pintype "passive"))
      (node (ref "C32") (pin "2") (pinfunction "2_2") (pintype "passive"))
      (node (ref "C35") (pin "1") (pinfunction "1_1") (pintype "passive"))
      (node (ref "C38") (pin "2") (pinfunction "2_2") (pintype "passive"))
      (node (ref "C39") (pin "2") (pinfunction "2_2") (pintype "passive"))
      (node (ref "C4") (pin "-") (pinfunction "-_-") (pintype "passive"))
      (node (ref "C40") (pin "2") (pinfunction "2_2") (pintype "passive"))
      (node (ref "C41") (pin "2") (pinfunction "2_2") (pintype "passive"))
      (node (ref "C42") (pin "2") (pinfunction "2_2") (pintype "passive"))
      (node (ref "C5") (pin "2") (pinfunction "2_2") (pintype "passive"))
      (node (ref "C56") (pin "1") (pinfunction "1_1") (pintype "passive"))
      (node (ref "C57") (pin "1") (pinfunction "1_1") (pintype "passive"))
      (node (ref "C59") (pin "2") (pinfunction "2_2") (pintype "passive"))
      (node (ref "C6") (pin "2") (pinfunction "2_2") (pintype "passive"))
      (node (ref "C61") (pin "1") (pinfunction "1_1") (pintype "passive"))
      (node (ref "C62") (pin "2") (pinfunction "2_2") (pintype "passive"))
      (node (ref "C64") (pin "2") (pinfunction "2_2") (pintype "passive"))
      (node (ref "C65") (pin "2") (pinfunction "2_2") (pintype "passive"))
      (node (ref "C7") (pin "2") (pinfunction "2_2") (pintype "passive"))
      (node (ref "C8") (pin "2") (pinfunction "2_2") (pintype "passive"))
      (node (ref "C9") (pin "1") (pinfunction "1_1") (pintype "passive"))
      (node (ref "CON1") (pin "4") (pinfunction "4_4") (pintype "passive"))
      (node (ref "CON1") (pin "5") (pinfunction "5_5") (pintype "passive"))
      (node (ref "CON5") (pin "4") (pinfunction "4_4") (pintype "passive"))
      (node (ref "CON5") (pin "5") (pinfunction "5_5") (pintype "passive"))
      (node (ref "D1") (pin "3") (pinfunction "3_3") (pintype "passive"))
      (node (ref "D2") (pin "3") (pinfunction "3_3") (pintype "passive"))
      (node (ref "L2") (pin "1") (pinfunction "1_1") (pintype "passive"))
      (node (ref "LED1") (pin "C") (pinfunction "C_C") (pintype "passive"))
      (node (ref "P2") (pin "GND") (pinfunction "GND_GND") (pintype "power_in"))
      (node (ref "P3") (pin "6") (pinfunction "VSS_6") (pintype "power_in"))
      (node (ref "Q2") (pin "2") (pinfunction "2_2") (pintype "bidirectional"))
      (node (ref "Q2") (pin "3") (pinfunction "3_3") (pintype "bidirectional"))
      (node (ref "Q3") (pin "2") (pinfunction "2_2") (pintype "bidirectional"))
      (node (ref "Q3") (pin "4") (pinfunction "4_4") (pintype "bidirectional"))
      (node (ref "R14") (pin "2") (pinfunction "2_2") (pintype "passive"))
      (node (ref "R17") (pin "2") (pinfunction "2_2") (pintype "passive"))
      (node (ref "R37") (pin "1") (pinfunction "1_1") (pintype "passive"))
      (node (ref "R7") (pin "2") (pinfunction "2_2") (pintype "passive"))
      (node (ref "R70") (pin "2") (pinfunction "2_2") (pintype "passive"))
      (node (ref "RM1") (pin "1.2") (pinfunction "2_1.2") (pintype "passive"))
      (node (ref "RM1") (pin "4.2") (pinfunction "2_4.2") (pintype "passive"))
      (node (ref "RM3") (pin "1.1") (pinfunction "1_1.1") (pintype "passive"))
      (node (ref "RM3") (pin "2.1") (pinfunction "1_2.1") (pintype "passive"))
      (node (ref "RM3") (pin "3.1") (pinfunction "1_3.1") (pintype "passive"))
      (node (ref "RM3") (pin "4.1") (pinfunction "1_4.1") (pintype "passive"))
      (node (ref "RM4") (pin "4.2") (pinfunction "2_4.2") (pintype "passive"))
      (node (ref "SJ3") (pin "1") (pinfunction "1_1") (pintype "passive"))
      (node (ref "TS1") (pin "P$1") (pinfunction "PP_P$1") (pintype "passive"))
      (node (ref "U1") (pin "2") (pinfunction "2_2") (pintype "power_in"))
      (node (ref "U2") (pin "6") (pinfunction "GND_6") (pintype "power_in"))
      (node (ref "U3") (pin "2") (pinfunction "2_2") (pintype "power_in"))
      (node (ref "U4") (pin "3") (pinfunction "GND_3") (pintype "bidirectional"))
      (node (ref "U4") (pin "TAB") (pinfunction "THERMAL_TAB") (pintype "bidirectional"))
      (node (ref "U5") (pin "107") (pinfunction "VSS_2_107") (pintype "power_in"))
      (node (ref "U5") (pin "120") (pinfunction "VSS_10_120") (pintype "power_in"))
      (node (ref "U5") (pin "130") (pinfunction "VSS_11_130") (pintype "power_in"))
      (node (ref "U5") (pin "16") (pinfunction "VSS_5_16") (pintype "power_in"))
      (node (ref "U5") (pin "38") (pinfunction "VSS_4_38") (pintype "power_in"))
      (node (ref "U5") (pin "51") (pinfunction "VSS_6_51") (pintype "power_in"))
      (node (ref "U5") (pin "61") (pinfunction "VSS_7_61") (pintype "power_in"))
      (node (ref "U5") (pin "83") (pinfunction "VSS_8_83") (pintype "power_in"))
      (node (ref "U5") (pin "94") (pinfunction "VSS_9_94") (pintype "power_in"))
      (node (ref "U6") (pin "3") (pinfunction "GND_3") (pintype "power_in"))
      (node (ref "U7") (pin "12") (pinfunction "GND_12") (pintype "passive"))
      (node (ref "U7") (pin "34") (pinfunction "GND_2_34") (pintype "passive"))
      (node (ref "U9") (pin "29") (pinfunction "GND_29") (pintype "bidirectional"))
      (node (ref "X2") (pin "2") (pinfunction "2_2") (pintype "passive"))
      (node (ref "X2") (pin "3") (pinfunction "3_3") (pintype "passive"))
      (node (ref "X3") (pin "GND") (pinfunction "VBUS_GND") (pintype "bidirectional"))
    )
    (net (code "105") (name "Net-(BTN1-0)") (class "Default")
      (node (ref "BTN1") (pin "P$1") (pinfunction "0_P$1") (pintype "passive"))
      (node (ref "C35") (pin "2") (pinfunction "2_2") (pintype "passive"))
      (node (ref "R19") (pin "1") (pinfunction "1_1") (pintype "passive"))
      (node (ref "R21") (pin "2") (pinfunction "2_2") (pintype "passive"))
      (node (ref "U6") (pin "1") (pinfunction "RESET_1") (pintype "output"))
    )
    (net (code "106") (name "Net-(C32-Pad1)") (class "Default")
      (node (ref "C32") (pin "1") (pinfunction "1_1") (pintype "passive"))
      (node (ref "Q1") (pin "1") (pinfunction "1_1") (pintype "passive"))
      (node (ref "R20") (pin "1") (pinfunction "1_1") (pintype "passive"))
    )
    (net (code "107") (name "Net-(C33-Pad2)") (class "Default")
      (node (ref "C33") (pin "2") (pinfunction "2_2") (pintype "passive"))
      (node (ref "Q2") (pin "4") (pinfunction "4_4") (pintype "bidirectional"))
    )
    (net (code "108") (name "Net-(C34-Pad2)") (class "Default")
      (node (ref "C34") (pin "2") (pinfunction "2_2") (pintype "passive"))
      (node (ref "Q2") (pin "1") (pinfunction "1_1") (pintype "bidirectional"))
    )
    (net (code "109") (name "Net-(C64-Pad1)") (class "Default")
      (node (ref "C64") (pin "1") (pinfunction "1_1") (pintype "passive"))
      (node (ref "Q3") (pin "3") (pinfunction "3_3") (pintype "bidirectional"))
      (node (ref "R67") (pin "1") (pinfunction "1_1") (pintype "passive"))
    )
    (net (code "110") (name "Net-(C66-Pad1)") (class "Default")
      (node (ref "C66") (pin "1") (pinfunction "1_1") (pintype "passive"))
      (node (ref "R63") (pin "1") (pinfunction "1_1") (pintype "passive"))
      (node (ref "R64") (pin "1") (pinfunction "1_1") (pintype "passive"))
    )
    (net (code "111") (name "Net-(C67-Pad1)") (class "Default")
      (node (ref "C67") (pin "1") (pinfunction "1_1") (pintype "passive"))
      (node (ref "R62") (pin "1") (pinfunction "1_1") (pintype "passive"))
      (node (ref "X1") (pin "R3") (pinfunction "R3_R3") (pintype "bidirectional"))
    )
    (net (code "112") (name "Net-(C68-Pad2)") (class "Default")
      (node (ref "C68") (pin "2") (pinfunction "2_2") (pintype "passive"))
      (node (ref "X1") (pin "R8") (pinfunction "R8_R8") (pintype "bidirectional"))
    )
    (net (code "113") (name "Net-(C69-Pad2)") (class "Default")
      (node (ref "C69") (pin "2") (pinfunction "2_2") (pintype "passive"))
      (node (ref "X1") (pin "R7") (pinfunction "R7_R7") (pintype "bidirectional"))
    )
    (net (code "114") (name "Net-(L2-Pad2)") (class "Default")
      (node (ref "L2") (pin "2") (pinfunction "2_2") (pintype "passive"))
      (node (ref "P2") (pin "GND1") (pinfunction "GND1_GND1") (pintype "input"))
      (node (ref "P2") (pin "GND2") (pinfunction "GND2_GND2") (pintype "input"))
      (node (ref "P2") (pin "GND3") (pinfunction "GND3_GND3") (pintype "input"))
      (node (ref "P2") (pin "GND4") (pinfunction "GND4_GND4") (pintype "input"))
    )
    (net (code "115") (name "Net-(LED-PadA)") (class "Default")
      (node (ref "LED") (pin "A") (pinfunction "A_A") (pintype "passive"))
      (node (ref "R35") (pin "1") (pinfunction "1_1") (pintype "passive"))
    )
    (net (code "116") (name "Net-(LED1-PadA)") (class "Default")
      (node (ref "LED1") (pin "A") (pinfunction "A_A") (pintype "passive"))
      (node (ref "R34") (pin "2") (pinfunction "2_2") (pintype "passive"))
    )
    (net (code "117") (name "Net-(P3-VDD)") (class "Default")
      (node (ref "C38") (pin "1") (pinfunction "1_1") (pintype "passive"))
      (node (ref "C39") (pin "1") (pinfunction "1_1") (pintype "passive"))
      (node (ref "L1") (pin "2") (pinfunction "2_2") (pintype "passive"))
      (node (ref "P3") (pin "4") (pinfunction "VDD_4") (pintype "power_in"))
    )
    (net (code "118") (name "Net-(R9-Pad2)") (class "Default")
      (node (ref "R9") (pin "2") (pinfunction "2_2") (pintype "passive"))
      (node (ref "U3") (pin "4") (pinfunction "4_4") (pintype "bidirectional"))
    )
    (net (code "119") (name "Net-(R10-Pad2)") (class "Default")
      (node (ref "R10") (pin "2") (pinfunction "2_2") (pintype "passive"))
      (node (ref "U3") (pin "6") (pinfunction "6_6") (pintype "bidirectional"))
    )
    (net (code "120") (name "Net-(R24-Pad2)") (class "Default")
      (node (ref "R24") (pin "2") (pinfunction "2_2") (pintype "passive"))
      (node (ref "U1") (pin "4") (pinfunction "4_4") (pintype "bidirectional"))
    )
    (net (code "121") (name "Net-(R25-Pad2)") (class "Default")
      (node (ref "R25") (pin "2") (pinfunction "2_2") (pintype "passive"))
      (node (ref "U1") (pin "6") (pinfunction "6_6") (pintype "bidirectional"))
    )
    (net (code "122") (name "Net-(R65-Pad1)") (class "Default")
      (node (ref "R65") (pin "1") (pinfunction "1_1") (pintype "passive"))
      (node (ref "X1") (pin "L3") (pinfunction "L3_L3") (pintype "bidirectional"))
    )
    (net (code "123") (name "Net-(R66-Pad1)") (class "Default")
      (node (ref "R66") (pin "1") (pinfunction "1_1") (pintype "passive"))
      (node (ref "X1") (pin "L1") (pinfunction "L1_L1") (pintype "bidirectional"))
    )
    (net (code "124") (name "Net-(RM3A-2)") (class "Default")
      (node (ref "RM3") (pin "1.2") (pinfunction "2_1.2") (pintype "passive"))
      (node (ref "U9") (pin "39") (pinfunction "RSVD3_39") (pintype "bidirectional"))
    )
    (net (code "125") (name "Net-(RM3B-2)") (class "Default")
      (node (ref "RM3") (pin "2.2") (pinfunction "2_2.2") (pintype "passive"))
      (node (ref "U9") (pin "40") (pinfunction "RSVD2_40") (pintype "bidirectional"))
    )
    (net (code "126") (name "Net-(RM3C-2)") (class "Default")
      (node (ref "RM3") (pin "3.2") (pinfunction "2_3.2") (pintype "passive"))
      (node (ref "U9") (pin "41") (pinfunction "RSVD1_41") (pintype "bidirectional"))
    )
    (net (code "127") (name "Net-(RM3D-2)") (class "Default")
      (node (ref "RM3") (pin "4.2") (pinfunction "2_4.2") (pintype "passive"))
      (node (ref "U9") (pin "42") (pinfunction "RSVD6_42") (pintype "bidirectional"))
    )
    (net (code "128") (name "Net-(RM4D-1)") (class "Default")
      (node (ref "RM4") (pin "4.1") (pinfunction "1_4.1") (pintype "passive"))
      (node (ref "U9") (pin "38") (pinfunction "RSVD_38") (pintype "bidirectional"))
    )
    (net (code "129") (name "Net-(SJ1-Pad3)") (class "Default")
      (node (ref "SJ1") (pin "3") (pinfunction "3_3") (pintype "passive"))
      (node (ref "X2") (pin "1") (pinfunction "1_1") (pintype "passive"))
    )
    (net (code "130") (name "Net-(U4-NR)") (class "Default")
      (node (ref "C42") (pin "1") (pinfunction "1_1") (pintype "passive"))
      (node (ref "U4") (pin "5") (pinfunction "NR_5") (pintype "bidirectional"))
    )
    (net (code "131") (name "Net-(U5-PC14)") (class "Default")
      (node (ref "C33") (pin "1") (pinfunction "1_1") (pintype "passive"))
      (node (ref "R22") (pin "2") (pinfunction "2_2") (pintype "passive"))
      (node (ref "U5") (pin "8") (pinfunction "PC14_8") (pintype "bidirectional"))
    )
    (net (code "132") (name "Net-(U5-PC15)") (class "Default")
      (node (ref "C34") (pin "1") (pinfunction "1_1") (pintype "passive"))
      (node (ref "R22") (pin "1") (pinfunction "1_1") (pintype "passive"))
      (node (ref "U5") (pin "9") (pinfunction "PC15_9") (pintype "bidirectional"))
    )
    (net (code "133") (name "Net-(U5-PH0)") (class "Default")
      (node (ref "C31") (pin "1") (pinfunction "1_1") (pintype "passive"))
      (node (ref "Q1") (pin "2") (pinfunction "2_2") (pintype "passive"))
      (node (ref "R18") (pin "2") (pinfunction "2_2") (pintype "passive"))
      (node (ref "U5") (pin "23") (pinfunction "PH0_23") (pintype "input"))
    )
    (net (code "134") (name "Net-(U5-PH1)") (class "Default")
      (node (ref "R18") (pin "1") (pinfunction "1_1") (pintype "passive"))
      (node (ref "R20") (pin "2") (pinfunction "2_2") (pintype "passive"))
      (node (ref "U5") (pin "24") (pinfunction "PH1_24") (pintype "output"))
    )
    (net (code "135") (name "Net-(U5-VCAP_1)") (class "Default")
      (node (ref "C13") (pin "2") (pinfunction "2_2") (pintype "passive"))
      (node (ref "U5") (pin "71") (pinfunction "VCAP_1_71") (pintype "output"))
    )
    (net (code "136") (name "Net-(U5-VCAP_2)") (class "Default")
      (node (ref "C27") (pin "2") (pinfunction "2_2") (pintype "passive"))
      (node (ref "U5") (pin "106") (pinfunction "VCAP_2_106") (pintype "output"))
    )
    (net (code "137") (name "Net-(U5-VDD_3)") (class "Default")
      (node (ref "C16") (pin "2") (pinfunction "2_2") (pintype "passive"))
      (node (ref "R11") (pin "1") (pinfunction "1_1") (pintype "passive"))
      (node (ref "R14") (pin "1") (pinfunction "1_1") (pintype "passive"))
      (node (ref "U5") (pin "143") (pinfunction "VDD_3_143") (pintype "power_in"))
    )
    (net (code "138") (name "Net-(U5-VREF+)") (class "Default")
      (node (ref "C30") (pin "2") (pinfunction "2_2") (pintype "passive"))
      (node (ref "R16") (pin "2") (pinfunction "2_2") (pintype "passive"))
      (node (ref "U5") (pin "32") (pinfunction "VREF+_32") (pintype "power_in"))
    )
    (net (code "139") (name "Net-(U9-1V2O)") (class "Default")
      (node (ref "C61") (pin "2") (pinfunction "2_2") (pintype "passive"))
      (node (ref "U9") (pin "22") (pinfunction "1V2O_22") (pintype "bidirectional"))
    )
    (net (code "140") (name "Net-(U9-EXRES1)") (class "Default")
      (node (ref "R69") (pin "1") (pinfunction "1_1") (pintype "passive"))
      (node (ref "U9") (pin "10") (pinfunction "EXRES1_10") (pintype "bidirectional"))
    )
    (net (code "141") (name "Net-(U9-RSVD5)") (class "Default")
      (node (ref "R70") (pin "1") (pinfunction "1_1") (pintype "passive"))
      (node (ref "U9") (pin "23") (pinfunction "RSVD5_23") (pintype "bidirectional"))
    )
    (net (code "142") (name "Net-(U9-TOCAP)") (class "Default")
      (node (ref "C60") (pin "2") (pinfunction "2_2") (pintype "passive"))
      (node (ref "U9") (pin "20") (pinfunction "TOCAP_20") (pintype "bidirectional"))
    )
    (net (code "143") (name "Net-(WKUP-1)") (class "Default")
      (node (ref "C37") (pin "1") (pinfunction "1_1") (pintype "passive"))
      (node (ref "R36") (pin "1") (pinfunction "1_1") (pintype "passive"))
      (node (ref "R37") (pin "2") (pinfunction "2_2") (pintype "passive"))
      (node (ref "WKUP") (pin "P$2") (pinfunction "1_P$2") (pintype "passive"))
    )
    (net (code "144") (name "unconnected-(P3-DAT1{slash}RES-Pad8)") (class "Default")
      (node (ref "P3") (pin "8") (pinfunction "DAT1/RES_8") (pintype "bidirectional"))
    )
    (net (code "145") (name "unconnected-(P3-DAT2{slash}RES-Pad1)") (class "Default")
      (node (ref "P3") (pin "1") (pinfunction "DAT2/RES_1") (pintype "bidirectional"))
    )
    (net (code "146") (name "unconnected-(U5-PB2-Pad48)") (class "Default")
      (node (ref "U5") (pin "48") (pinfunction "PB2_48") (pintype "bidirectional"))
    )
    (net (code "147") (name "unconnected-(U5-PB4-Pad134)") (class "Default")
      (node (ref "U5") (pin "134") (pinfunction "PB4_134") (pintype "bidirectional"))
    )
    (net (code "148") (name "unconnected-(U5-PC6-Pad96)") (class "Default")
      (node (ref "U5") (pin "96") (pinfunction "PC6_96") (pintype "bidirectional"))
    )
    (net (code "149") (name "unconnected-(U5-PC7-Pad97)") (class "Default")
      (node (ref "U5") (pin "97") (pinfunction "PC7_97") (pintype "bidirectional"))
    )
    (net (code "150") (name "unconnected-(U5-PC8-Pad98)") (class "Default")
      (node (ref "U5") (pin "98") (pinfunction "PC8_98") (pintype "bidirectional"))
    )
    (net (code "151") (name "unconnected-(U5-PC9-Pad99)") (class "Default")
      (node (ref "U5") (pin "99") (pinfunction "PC9_99") (pintype "bidirectional"))
    )
    (net (code "152") (name "unconnected-(U5-PD2-Pad116)") (class "Default")
      (node (ref "U5") (pin "116") (pinfunction "PD2_116") (pintype "bidirectional"))
    )
    (net (code "153") (name "unconnected-(U5-PD3-Pad117)") (class "Default")
      (node (ref "U5") (pin "117") (pinfunction "PD3_117") (pintype "bidirectional"))
    )
    (net (code "154") (name "unconnected-(U5-PD6-Pad122)") (class "Default")
      (node (ref "U5") (pin "122") (pinfunction "PD6_122") (pintype "bidirectional"))
    )
    (net (code "155") (name "unconnected-(U5-PD8-Pad77)") (class "Default")
      (node (ref "U5") (pin "77") (pinfunction "PD8_77") (pintype "bidirectional"))
    )
    (net (code "156") (name "unconnected-(U5-PD9-Pad78)") (class "Default")
      (node (ref "U5") (pin "78") (pinfunction "PD9_78") (pintype "bidirectional"))
    )
    (net (code "157") (name "unconnected-(U5-PD10-Pad79)") (class "Default")
      (node (ref "U5") (pin "79") (pinfunction "PD10_79") (pintype "bidirectional"))
    )
    (net (code "158") (name "unconnected-(U5-PE0-Pad141)") (class "Default")
      (node (ref "U5") (pin "141") (pinfunction "PE0_141") (pintype "bidirectional"))
    )
    (net (code "159") (name "unconnected-(U5-PE1-Pad142)") (class "Default")
      (node (ref "U5") (pin "142") (pinfunction "PE1_142") (pintype "bidirectional"))
    )
    (net (code "160") (name "unconnected-(U5-PE2-Pad1)") (class "Default")
      (node (ref "U5") (pin "1") (pinfunction "PE2_1") (pintype "bidirectional"))
    )
    (net (code "161") (name "unconnected-(U5-PE4-Pad3)") (class "Default")
      (node (ref "U5") (pin "3") (pinfunction "PE4_3") (pintype "bidirectional"))
    )
    (net (code "162") (name "unconnected-(U5-PE11-Pad64)") (class "Default")
      (node (ref "U5") (pin "64") (pinfunction "PE11_64") (pintype "bidirectional"))
    )
    (net (code "163") (name "unconnected-(U5-PE12-Pad65)") (class "Default")
      (node (ref "U5") (pin "65") (pinfunction "PE12_65") (pintype "bidirectional"))
    )
    (net (code "164") (name "unconnected-(U5-PE13-Pad66)") (class "Default")
      (node (ref "U5") (pin "66") (pinfunction "PE13_66") (pintype "bidirectional"))
    )
    (net (code "165") (name "unconnected-(U5-PE14-Pad67)") (class "Default")
      (node (ref "U5") (pin "67") (pinfunction "PE14_67") (pintype "bidirectional"))
    )
    (net (code "166") (name "unconnected-(U5-PE15-Pad68)") (class "Default")
      (node (ref "U5") (pin "68") (pinfunction "PE15_68") (pintype "bidirectional"))
    )
    (net (code "167") (name "unconnected-(U5-PF6-Pad18)") (class "Default")
      (node (ref "U5") (pin "18") (pinfunction "PF6_18") (pintype "bidirectional"))
    )
    (net (code "168") (name "unconnected-(U5-PF7-Pad19)") (class "Default")
      (node (ref "U5") (pin "19") (pinfunction "PF7_19") (pintype "bidirectional"))
    )
    (net (code "169") (name "unconnected-(U5-PF8-Pad20)") (class "Default")
      (node (ref "U5") (pin "20") (pinfunction "PF8_20") (pintype "bidirectional"))
    )
    (net (code "170") (name "unconnected-(U5-PF9-Pad21)") (class "Default")
      (node (ref "U5") (pin "21") (pinfunction "PF9_21") (pintype "bidirectional"))
    )
    (net (code "171") (name "unconnected-(U5-PF10-Pad22)") (class "Default")
      (node (ref "U5") (pin "22") (pinfunction "PF10_22") (pintype "bidirectional"))
    )
    (net (code "172") (name "unconnected-(U5-PF11-Pad49)") (class "Default")
      (node (ref "U5") (pin "49") (pinfunction "PF11_49") (pintype "bidirectional"))
    )
    (net (code "173") (name "unconnected-(U5-PG6-Pad91)") (class "Default")
      (node (ref "U5") (pin "91") (pinfunction "PG6_91") (pintype "bidirectional"))
    )
    (net (code "174") (name "unconnected-(U5-PG7-Pad92)") (class "Default")
      (node (ref "U5") (pin "92") (pinfunction "PG7_92") (pintype "bidirectional"))
    )
    (net (code "175") (name "unconnected-(U5-PG8-Pad93)") (class "Default")
      (node (ref "U5") (pin "93") (pinfunction "PG8_93") (pintype "bidirectional"))
    )
    (net (code "176") (name "unconnected-(U5-PG10-Pad125)") (class "Default")
      (node (ref "U5") (pin "125") (pinfunction "PG10_125") (pintype "bidirectional"))
    )
    (net (code "177") (name "unconnected-(U5-PG11-Pad126)") (class "Default")
      (node (ref "U5") (pin "126") (pinfunction "PG11_126") (pintype "bidirectional"))
    )
    (net (code "178") (name "unconnected-(U5-PG12-Pad127)") (class "Default")
      (node (ref "U5") (pin "127") (pinfunction "PG12_127") (pintype "bidirectional"))
    )
    (net (code "179") (name "unconnected-(U5-PG13-Pad128)") (class "Default")
      (node (ref "U5") (pin "128") (pinfunction "PG13_128") (pintype "bidirectional"))
    )
    (net (code "180") (name "unconnected-(U5-PG14-Pad129)") (class "Default")
      (node (ref "U5") (pin "129") (pinfunction "PG14_129") (pintype "bidirectional"))
    )
    (net (code "181") (name "unconnected-(U9-DNC-Pad7)") (class "Default")
      (node (ref "U9") (pin "7") (pinfunction "DNC_7") (pintype "bidirectional"))
    )
    (net (code "182") (name "unconnected-(U9-DUPLED-Pad26)") (class "Default")
      (node (ref "U9") (pin "26") (pinfunction "DUPLED_26") (pintype "bidirectional"))
    )
    (net (code "183") (name "unconnected-(U9-NC-Pad47)") (class "Default")
      (node (ref "U9") (pin "47") (pinfunction "NC_47") (pintype "bidirectional"))
    )
    (net (code "184") (name "unconnected-(U9-NC1-Pad46)") (class "Default")
      (node (ref "U9") (pin "46") (pinfunction "NC1_46") (pintype "bidirectional"))
    )
    (net (code "185") (name "unconnected-(U9-NC2-Pad13)") (class "Default")
      (node (ref "U9") (pin "13") (pinfunction "NC2_13") (pintype "bidirectional"))
    )
    (net (code "186") (name "unconnected-(U9-NC3-Pad12)") (class "Default")
      (node (ref "U9") (pin "12") (pinfunction "NC3_12") (pintype "bidirectional"))
    )
    (net (code "187") (name "unconnected-(U9-SPDLED-Pad24)") (class "Default")
      (node (ref "U9") (pin "24") (pinfunction "SPDLED_24") (pintype "bidirectional"))
    )
    (net (code "188") (name "unconnected-(U9-VBG-Pad18)") (class "Default")
      (node (ref "U9") (pin "18") (pinfunction "VBG_18") (pintype "bidirectional"))
    )
  )
)
